# GTM900-breakout_v3.net
KiCad netlist of a schematic drawn in EAGLE
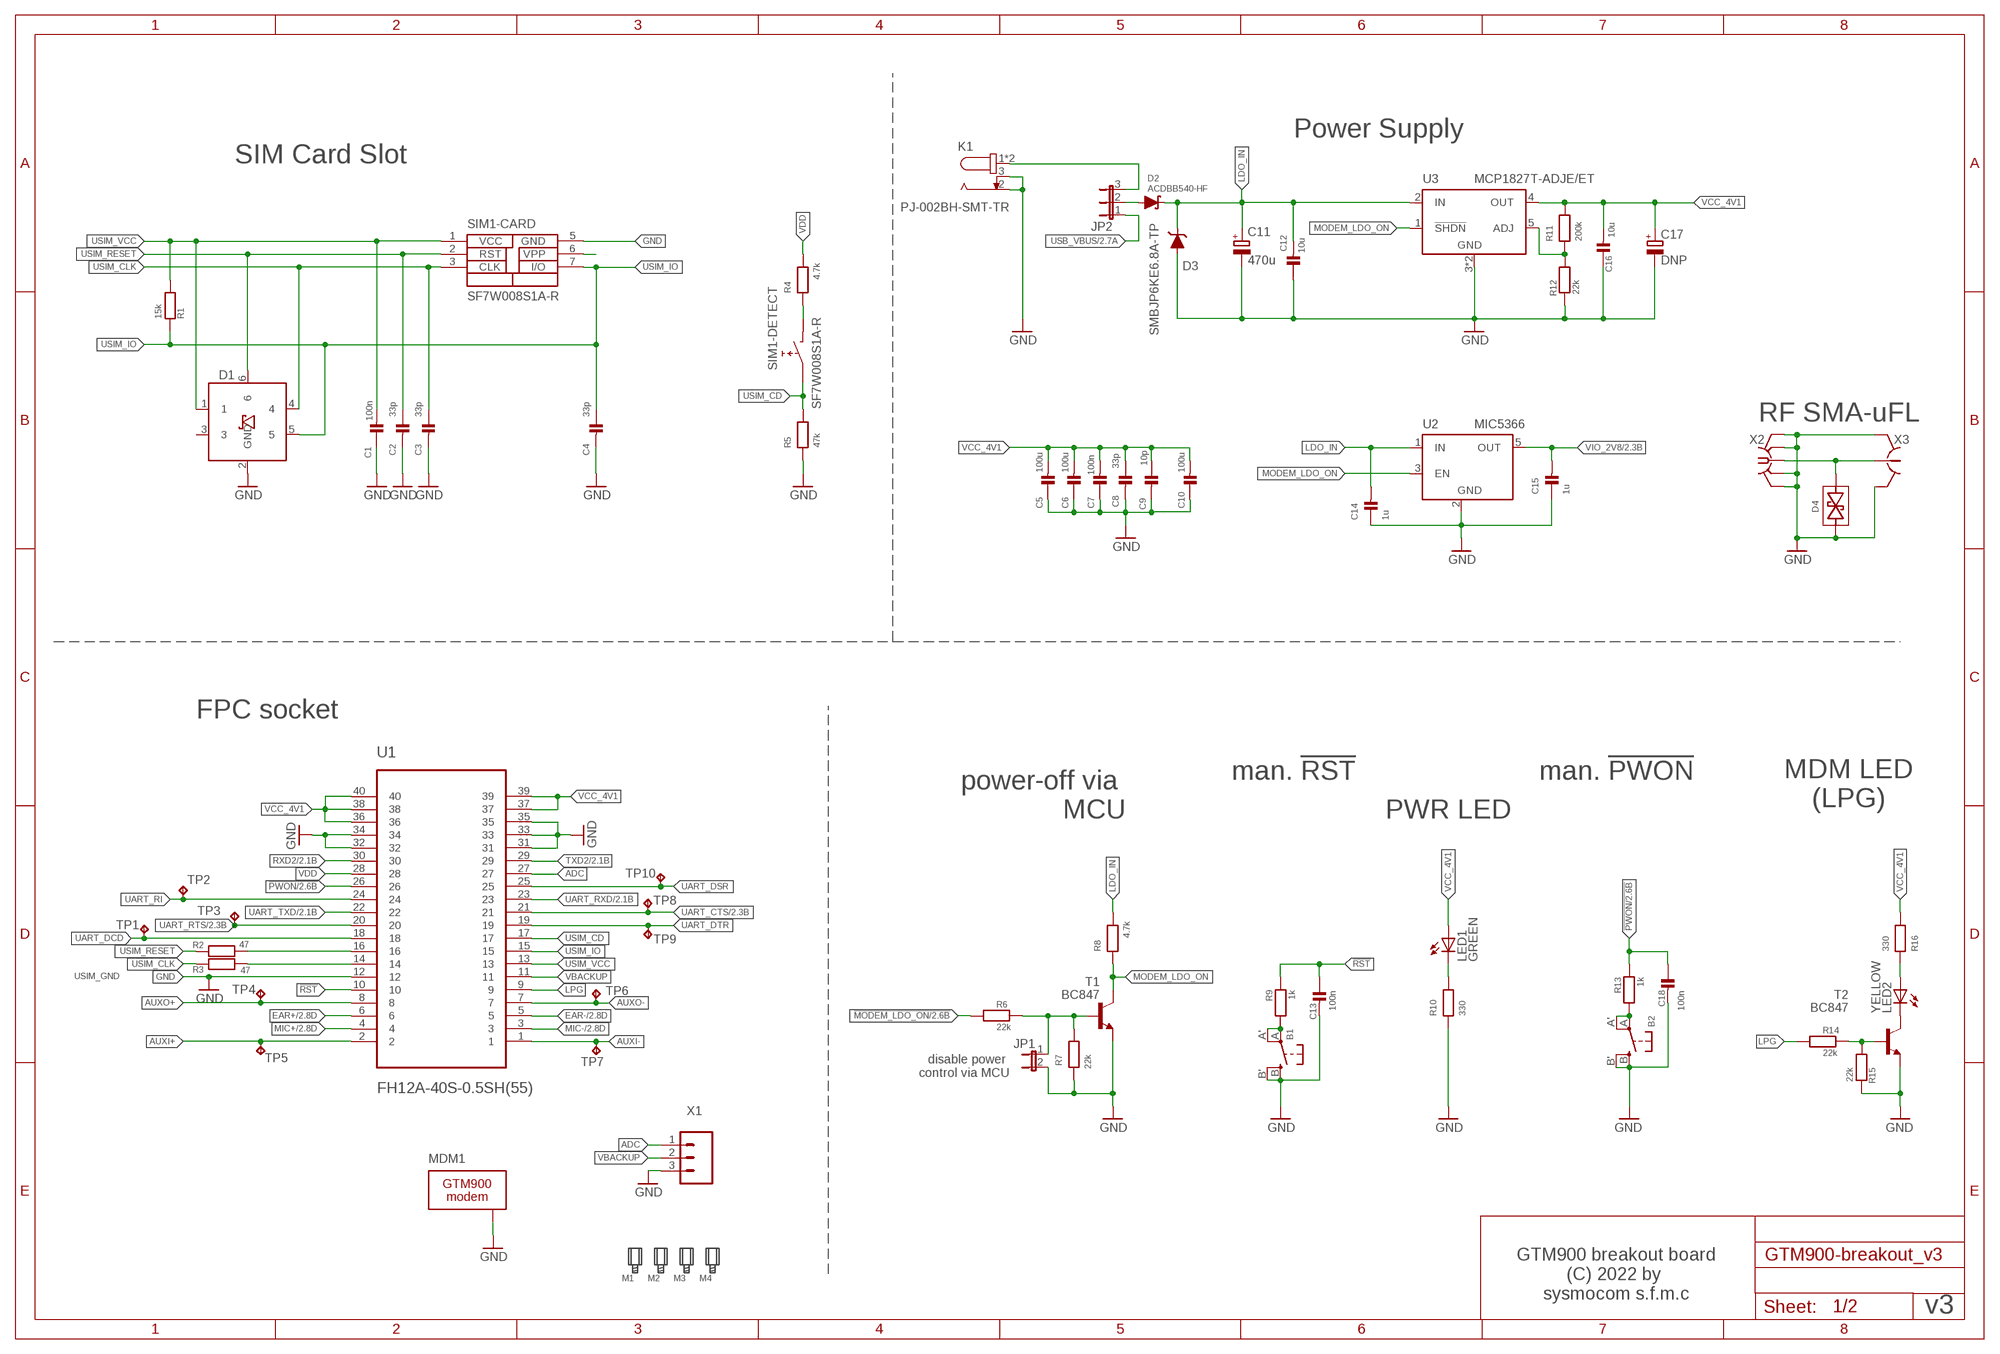
[diagram p0: schematic, sheet 1]
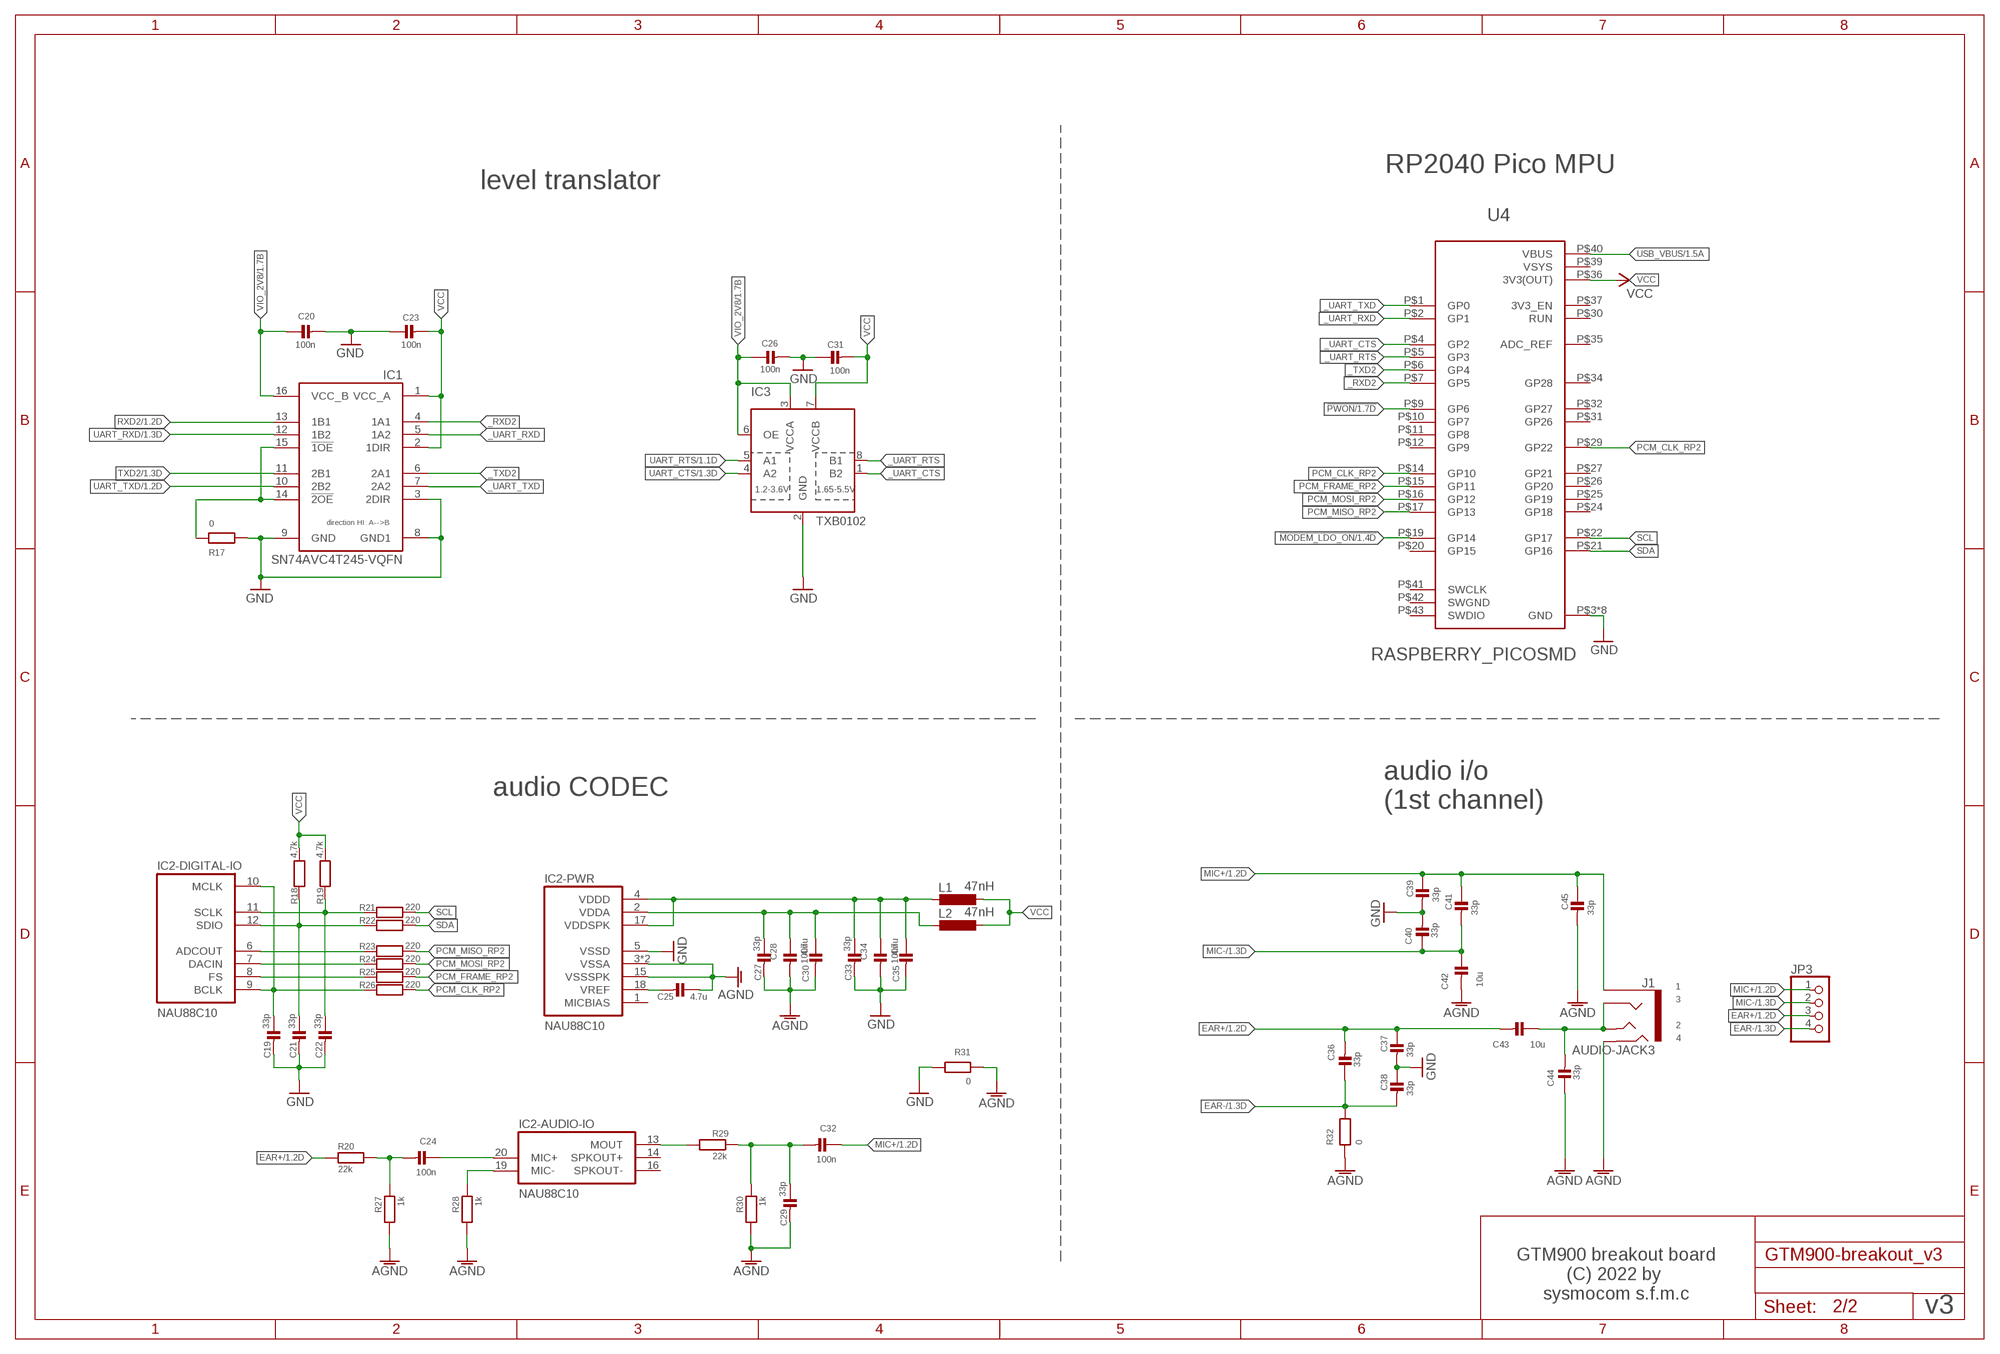
[diagram p1: schematic, sheet 2]

(export (version "E")
  (design (tool "Eeschema 10.0.6"))
  (components
    (comp (ref "C19")
      (value "33p")
      (footprint "eagle-import:_0402")
      (description "CAP CER 33PF 50V NP0 0402")
      (fields
        (field (name "MANUFACTURER") "Samsung Electro-Mechanics America, Inc.")
        (field (name "MANUFACTURERPARTNUMBER") "CL05C330JB5NNNC")
      )
      (libsource (lib "eagle-import") (part "CAP_CERAMIC_0402"))
    )
    (comp (ref "C20")
      (value "100n")
      (footprint "eagle-import:_0603")
      (description "CAP CER 0.1UF 16V X5R 0201")
      (fields
        (field (name "MANUFACTURER") "Murata Electronics")
        (field (name "MANUFACTURERPARTNUMBER") "GRM033R61C104KE84D")
      )
      (libsource (lib "eagle-import") (part "CAP_CERAMIC_0603"))
    )
    (comp (ref "C21")
      (value "33p")
      (footprint "eagle-import:_0402")
      (description "CAP CER 33PF 50V NP0 0402")
      (fields
        (field (name "MANUFACTURER") "Samsung Electro-Mechanics America, Inc.")
        (field (name "MANUFACTURERPARTNUMBER") "CL05C330JB5NNNC")
      )
      (libsource (lib "eagle-import") (part "CAP_CERAMIC_0402"))
    )
    (comp (ref "C22")
      (value "33p")
      (footprint "eagle-import:_0402")
      (description "CAP CER 33PF 50V NP0 0402")
      (fields
        (field (name "MANUFACTURER") "Samsung Electro-Mechanics America, Inc.")
        (field (name "MANUFACTURERPARTNUMBER") "CL05C330JB5NNNC")
      )
      (libsource (lib "eagle-import") (part "CAP_CERAMIC_0402"))
    )
    (comp (ref "C23")
      (value "100n")
      (footprint "eagle-import:_0603")
      (description "CAP CER 0.1UF 16V X5R 0201")
      (fields
        (field (name "MANUFACTURER") "Murata Electronics")
        (field (name "MANUFACTURERPARTNUMBER") "GRM033R61C104KE84D")
      )
      (libsource (lib "eagle-import") (part "CAP_CERAMIC_0603"))
    )
    (comp (ref "C24")
      (value "100n")
      (footprint "eagle-import:_0603")
      (description "CAP CER 0.1UF 16V X5R 0201")
      (fields
        (field (name "MANUFACTURER") "Murata Electronics")
        (field (name "MANUFACTURERPARTNUMBER") "GRM033R61C104KE84D")
      )
      (libsource (lib "eagle-import") (part "CAP_CERAMIC_0603"))
    )
    (comp (ref "C25")
      (value "4.7u")
      (footprint "eagle-import:_0603")
      (description "NO DESCRIPTION")
      (fields
        (field (name "MANUFACTURER") "UNKNOWN MANUFACTURER")
        (field (name "MANUFACTURERPARTNUMBER") "UNKNOWN MANUFACTURER PART NUMBER")
      )
      (libsource (lib "eagle-import") (part "CAP_CERAMIC_0603"))
    )
    (comp (ref "C26")
      (value "100n")
      (footprint "eagle-import:_0603")
      (description "CAP CER 0.1UF 16V X5R 0201")
      (fields
        (field (name "MANUFACTURER") "Murata Electronics")
        (field (name "MANUFACTURERPARTNUMBER") "GRM033R61C104KE84D")
      )
      (libsource (lib "eagle-import") (part "CAP_CERAMIC_0603"))
    )
    (comp (ref "C27")
      (value "33p")
      (footprint "eagle-import:_0402")
      (description "CAP CER 33PF 50V NP0 0402")
      (fields
        (field (name "MANUFACTURER") "Samsung Electro-Mechanics America, Inc.")
        (field (name "MANUFACTURERPARTNUMBER") "CL05C330JB5NNNC")
      )
      (libsource (lib "eagle-import") (part "CAP_CERAMIC_0402"))
    )
    (comp (ref "C28")
      (value "100n")
      (footprint "eagle-import:_0603")
      (description "CAP CER 0.1UF 16V X5R 0201")
      (fields
        (field (name "MANUFACTURER") "Murata Electronics")
        (field (name "MANUFACTURERPARTNUMBER") "GRM033R61C104KE84D")
      )
      (libsource (lib "eagle-import") (part "CAP_CERAMIC_0603"))
    )
    (comp (ref "C29")
      (value "33p")
      (footprint "eagle-import:_0402")
      (description "CAP CER 33PF 50V NP0 0402")
      (fields
        (field (name "MANUFACTURER") "Samsung Electro-Mechanics America, Inc.")
        (field (name "MANUFACTURERPARTNUMBER") "CL05C330JB5NNNC")
      )
      (libsource (lib "eagle-import") (part "CAP_CERAMIC_0402"))
    )
    (comp (ref "C30")
      (value "4.7u")
      (footprint "eagle-import:_0603")
      (description "NO DESCRIPTION")
      (fields
        (field (name "MANUFACTURER") "UNKNOWN MANUFACTURER")
        (field (name "MANUFACTURERPARTNUMBER") "UNKNOWN MANUFACTURER PART NUMBER")
      )
      (libsource (lib "eagle-import") (part "CAP_CERAMIC_0603"))
    )
    (comp (ref "C31")
      (value "100n")
      (footprint "eagle-import:_0603")
      (description "CAP CER 0.1UF 16V X5R 0201")
      (fields
        (field (name "MANUFACTURER") "Murata Electronics")
        (field (name "MANUFACTURERPARTNUMBER") "GRM033R61C104KE84D")
      )
      (libsource (lib "eagle-import") (part "CAP_CERAMIC_0603"))
    )
    (comp (ref "C32")
      (value "100n")
      (footprint "eagle-import:_0603")
      (description "CAP CER 0.1UF 16V X5R 0201")
      (fields
        (field (name "MANUFACTURER") "Murata Electronics")
        (field (name "MANUFACTURERPARTNUMBER") "GRM033R61C104KE84D")
      )
      (libsource (lib "eagle-import") (part "CAP_CERAMIC_0603"))
    )
    (comp (ref "C33")
      (value "33p")
      (footprint "eagle-import:_0402")
      (description "CAP CER 33PF 50V NP0 0402")
      (fields
        (field (name "MANUFACTURER") "Samsung Electro-Mechanics America, Inc.")
        (field (name "MANUFACTURERPARTNUMBER") "CL05C330JB5NNNC")
      )
      (libsource (lib "eagle-import") (part "CAP_CERAMIC_0402"))
    )
    (comp (ref "C34")
      (value "100n")
      (footprint "eagle-import:_0603")
      (description "CAP CER 0.1UF 16V X5R 0201")
      (fields
        (field (name "MANUFACTURER") "Murata Electronics")
        (field (name "MANUFACTURERPARTNUMBER") "GRM033R61C104KE84D")
      )
      (libsource (lib "eagle-import") (part "CAP_CERAMIC_0603"))
    )
    (comp (ref "C35")
      (value "4.7u")
      (footprint "eagle-import:_0603")
      (description "NO DESCRIPTION")
      (fields
        (field (name "MANUFACTURER") "UNKNOWN MANUFACTURER")
        (field (name "MANUFACTURERPARTNUMBER") "UNKNOWN MANUFACTURER PART NUMBER")
      )
      (libsource (lib "eagle-import") (part "CAP_CERAMIC_0603"))
    )
    (comp (ref "C36")
      (value "33p")
      (footprint "eagle-import:_0402")
      (description "CAP CER 33PF 50V NP0 0402")
      (fields
        (field (name "MANUFACTURER") "Samsung Electro-Mechanics America, Inc.")
        (field (name "MANUFACTURERPARTNUMBER") "CL05C330JB5NNNC")
      )
      (libsource (lib "eagle-import") (part "CAP_CERAMIC_0402"))
    )
    (comp (ref "C37")
      (value "33p")
      (footprint "eagle-import:_0402")
      (description "CAP CER 33PF 50V NP0 0402")
      (fields
        (field (name "MANUFACTURER") "Samsung Electro-Mechanics America, Inc.")
        (field (name "MANUFACTURERPARTNUMBER") "CL05C330JB5NNNC")
      )
      (libsource (lib "eagle-import") (part "CAP_CERAMIC_0402"))
    )
    (comp (ref "C38")
      (value "33p")
      (footprint "eagle-import:_0402")
      (description "CAP CER 33PF 50V NP0 0402")
      (fields
        (field (name "MANUFACTURER") "Samsung Electro-Mechanics America, Inc.")
        (field (name "MANUFACTURERPARTNUMBER") "CL05C330JB5NNNC")
      )
      (libsource (lib "eagle-import") (part "CAP_CERAMIC_0402"))
    )
    (comp (ref "C39")
      (value "33p")
      (footprint "eagle-import:_0402")
      (description "CAP CER 33PF 50V NP0 0402")
      (fields
        (field (name "MANUFACTURER") "Samsung Electro-Mechanics America, Inc.")
        (field (name "MANUFACTURERPARTNUMBER") "CL05C330JB5NNNC")
      )
      (libsource (lib "eagle-import") (part "CAP_CERAMIC_0402"))
    )
    (comp (ref "C40")
      (value "33p")
      (footprint "eagle-import:_0402")
      (description "CAP CER 33PF 50V NP0 0402")
      (fields
        (field (name "MANUFACTURER") "Samsung Electro-Mechanics America, Inc.")
        (field (name "MANUFACTURERPARTNUMBER") "CL05C330JB5NNNC")
      )
      (libsource (lib "eagle-import") (part "CAP_CERAMIC_0402"))
    )
    (comp (ref "C41")
      (value "33p")
      (footprint "eagle-import:_0402")
      (description "CAP CER 33PF 50V NP0 0402")
      (fields
        (field (name "MANUFACTURER") "Samsung Electro-Mechanics America, Inc.")
        (field (name "MANUFACTURERPARTNUMBER") "CL05C330JB5NNNC")
      )
      (libsource (lib "eagle-import") (part "CAP_CERAMIC_0402"))
    )
    (comp (ref "C42")
      (value "10u")
      (footprint "eagle-import:_0805")
      (description "CAP CER 10UF 16V X5R 0805")
      (fields
        (field (name "MANUFACTURER") "Murata Electronics")
        (field (name "MANUFACTURERPARTNUMBER") "GRM21BR61C106KE15K")
      )
      (libsource (lib "eagle-import") (part "CAP_CERAMIC_0805"))
    )
    (comp (ref "C43")
      (value "10u")
      (footprint "eagle-import:_0805")
      (description "CAP CER 10UF 16V X5R 0805")
      (fields
        (field (name "MANUFACTURER") "Murata Electronics")
        (field (name "MANUFACTURERPARTNUMBER") "GRM21BR61C106KE15K")
      )
      (libsource (lib "eagle-import") (part "CAP_CERAMIC_0805"))
    )
    (comp (ref "C44")
      (value "33p")
      (footprint "eagle-import:_0402")
      (description "CAP CER 33PF 50V NP0 0402")
      (fields
        (field (name "MANUFACTURER") "Samsung Electro-Mechanics America, Inc.")
        (field (name "MANUFACTURERPARTNUMBER") "CL05C330JB5NNNC")
      )
      (libsource (lib "eagle-import") (part "CAP_CERAMIC_0402"))
    )
    (comp (ref "C45")
      (value "33p")
      (footprint "eagle-import:_0402")
      (description "CAP CER 33PF 50V NP0 0402")
      (fields
        (field (name "MANUFACTURER") "Samsung Electro-Mechanics America, Inc.")
        (field (name "MANUFACTURERPARTNUMBER") "CL05C330JB5NNNC")
      )
      (libsource (lib "eagle-import") (part "CAP_CERAMIC_0402"))
    )
    (comp (ref "IC1")
      (value "SN74AVC4T245-VQFN")
      (footprint "eagle-import:VQFN-N16")
      (description "NO DESCRIPTION")
      (fields
        (field (name "MANUFACTURER") "UNKNOWN MANUFACTURER")
        (field (name "MANUFACTURERPARTNUMBER") "UNKNOWN MANUFACTURER PART NUMBER")
      )
      (libsource (lib "eagle-import") (part "SN74AVC4T245-VQFN"))
    )
    (comp (ref "IC2")
      (value "NAU88C10")
      (footprint "eagle-import:QFN20")
      (description "NO DESCRIPTION")
      (fields
        (field (name "CLASS") "UNKNOWN CLASS")
        (field (name "LINK") "UNKNOWN LINK")
        (field (name "MANUFACTURER") "UNKNOWN MANUFACTURER")
        (field (name "MANUFACTURERPARTNUMBER") "UNKNOWN MANUFACTURER PART NUMBER")
        (field (name "POPULATED") "TRUE")
        (field (name "ROHSCERTIFICATE") "UNKNOWN ROHS CERTIFICATE")
        (field (name "SOURCE") "UNKNOWN SOURCE")
        (field (name "SOURCEPARTNUMBER") "UNKNOWN SOURCE PART NUMBER")
      )
      (libsource (lib "eagle-import") (part "NAU88C10"))
    )
    (comp (ref "IC3")
      (value "TXB0102")
      (footprint "eagle-import:VSSOP-8")
      (description "NO DESCRIPTION")
      (fields
        (field (name "MANUFACTURER") "UNKNOWN MANUFACTURER")
        (field (name "MANUFACTURERPARTNUMBER") "UNKNOWN MANUFACTURER PART NUMBER")
      )
      (libsource (lib "eagle-import") (part "TXB0102"))
    )
    (comp (ref "J1")
      (value "AUDIO-JACK3")
      (footprint "eagle-import:AUDIO-JACK-TRRS-SMD")
      (description "AUDIO JACK, 3.5 MM, RT, 4 CONDUC")
      (fields
        (field (name "MANUFACTURER") "CUI Devices")
        (field (name "MANUFACTURERPARTNUMBER") "SJ2-3574A-SMT-TR")
      )
      (libsource (lib "eagle-import") (part "AUDIO-JACK3"))
    )
    (comp (ref "JP3")
      (value "HEADER-1X476MIL")
      (footprint "eagle-import:1X04_ROUND_76")
      (description "NO DESCRIPTION")
      (fields
        (field (name "MANUFACTURER") "UNKNOWN MANUFACTURER")
        (field (name "MANUFACTURERPARTNUMBER") "UNKNOWN MANUFACTURER PART NUMBER")
      )
      (libsource (lib "eagle-import") (part "HEADER-1X476MIL"))
    )
    (comp (ref "L1")
      (value "47nH")
      (footprint "eagle-import:_0603")
      (description "NO DESCRIPTION")
      (fields
        (field (name "MANUFACTURER") "UNKNOWN MANUFACTURER")
        (field (name "MANUFACTURERPARTNUMBER") "UNKNOWN MANUFACTURER PART NUMBER")
      )
      (libsource (lib "eagle-import") (part "INDUCTOR_0603"))
    )
    (comp (ref "L2")
      (value "47nH")
      (footprint "eagle-import:_0603")
      (description "NO DESCRIPTION")
      (fields
        (field (name "MANUFACTURER") "UNKNOWN MANUFACTURER")
        (field (name "MANUFACTURERPARTNUMBER") "UNKNOWN MANUFACTURER PART NUMBER")
      )
      (libsource (lib "eagle-import") (part "INDUCTOR_0603"))
    )
    (comp (ref "R17")
      (value "0")
      (footprint "eagle-import:_0603")
      (description "RES 0 OHM JUMPER 1/16W 0402")
      (fields
        (field (name "MANUFACTURER") "Stackpole Electronics Inc")
        (field (name "MANUFACTURERPARTNUMBER") "RMCF0402ZT0R00")
      )
      (libsource (lib "eagle-import") (part "RESISTOR_0603"))
    )
    (comp (ref "R18")
      (value "4,7k")
      (footprint "eagle-import:_0603")
      (description "NO DESCRIPTION")
      (fields
        (field (name "MANUFACTURER") "UNKNOWN MANUFACTURER")
        (field (name "MANUFACTURERPARTNUMBER") "UNKNOWN MANUFACTURER PART NUMBER")
      )
      (libsource (lib "eagle-import") (part "RESISTOR_0603"))
    )
    (comp (ref "R19")
      (value "4,7k")
      (footprint "eagle-import:_0603")
      (description "NO DESCRIPTION")
      (fields
        (field (name "MANUFACTURER") "UNKNOWN MANUFACTURER")
        (field (name "MANUFACTURERPARTNUMBER") "UNKNOWN MANUFACTURER PART NUMBER")
      )
      (libsource (lib "eagle-import") (part "RESISTOR_0603"))
    )
    (comp (ref "R20")
      (value "22k")
      (footprint "eagle-import:_0603")
      (description "RES SMD 22K OHM 1%% 1/10W 0603")
      (fields (field (name "MANUFACTURER") "Yageo") (field (name "MANUFACTURERPARTNUMBER") "RC0603FR-0722KL"))
      (libsource (lib "eagle-import") (part "RESISTOR_0603"))
    )
    (comp (ref "R21")
      (value "220")
      (footprint "eagle-import:_0603")
      (description "NO DESCRIPTION")
      (fields
        (field (name "MANUFACTURER") "UNKNOWN MANUFACTURER")
        (field (name "MANUFACTURERPARTNUMBER") "UNKNOWN MANUFACTURER PART NUMBER")
      )
      (libsource (lib "eagle-import") (part "RESISTOR_0603"))
    )
    (comp (ref "R22")
      (value "220")
      (footprint "eagle-import:_0603")
      (description "NO DESCRIPTION")
      (fields
        (field (name "MANUFACTURER") "UNKNOWN MANUFACTURER")
        (field (name "MANUFACTURERPARTNUMBER") "UNKNOWN MANUFACTURER PART NUMBER")
      )
      (libsource (lib "eagle-import") (part "RESISTOR_0603"))
    )
    (comp (ref "R23")
      (value "220")
      (footprint "eagle-import:_0603")
      (description "NO DESCRIPTION")
      (fields
        (field (name "MANUFACTURER") "UNKNOWN MANUFACTURER")
        (field (name "MANUFACTURERPARTNUMBER") "UNKNOWN MANUFACTURER PART NUMBER")
      )
      (libsource (lib "eagle-import") (part "RESISTOR_0603"))
    )
    (comp (ref "R24")
      (value "220")
      (footprint "eagle-import:_0603")
      (description "NO DESCRIPTION")
      (fields
        (field (name "MANUFACTURER") "UNKNOWN MANUFACTURER")
        (field (name "MANUFACTURERPARTNUMBER") "UNKNOWN MANUFACTURER PART NUMBER")
      )
      (libsource (lib "eagle-import") (part "RESISTOR_0603"))
    )
    (comp (ref "R25")
      (value "220")
      (footprint "eagle-import:_0603")
      (description "NO DESCRIPTION")
      (fields
        (field (name "MANUFACTURER") "UNKNOWN MANUFACTURER")
        (field (name "MANUFACTURERPARTNUMBER") "UNKNOWN MANUFACTURER PART NUMBER")
      )
      (libsource (lib "eagle-import") (part "RESISTOR_0603"))
    )
    (comp (ref "R26")
      (value "220")
      (footprint "eagle-import:_0603")
      (description "NO DESCRIPTION")
      (fields
        (field (name "MANUFACTURER") "UNKNOWN MANUFACTURER")
        (field (name "MANUFACTURERPARTNUMBER") "UNKNOWN MANUFACTURER PART NUMBER")
      )
      (libsource (lib "eagle-import") (part "RESISTOR_0603"))
    )
    (comp (ref "R27")
      (value "1k")
      (footprint "eagle-import:_0603")
      (description "NO DESCRIPTION")
      (fields
        (field (name "MANUFACTURER") "UNKNOWN MANUFACTURER")
        (field (name "MANUFACTURERPARTNUMBER") "UNKNOWN MANUFACTURER PART NUMBER")
      )
      (libsource (lib "eagle-import") (part "RESISTOR_0603"))
    )
    (comp (ref "R28")
      (value "1k")
      (footprint "eagle-import:_0603")
      (description "NO DESCRIPTION")
      (fields
        (field (name "MANUFACTURER") "UNKNOWN MANUFACTURER")
        (field (name "MANUFACTURERPARTNUMBER") "UNKNOWN MANUFACTURER PART NUMBER")
      )
      (libsource (lib "eagle-import") (part "RESISTOR_0603"))
    )
    (comp (ref "R29")
      (value "22k")
      (footprint "eagle-import:_0603")
      (description "RES SMD 22K OHM 1%% 1/10W 0603")
      (fields (field (name "MANUFACTURER") "Yageo") (field (name "MANUFACTURERPARTNUMBER") "RC0603FR-0722KL"))
      (libsource (lib "eagle-import") (part "RESISTOR_0603"))
    )
    (comp (ref "R30")
      (value "1k")
      (footprint "eagle-import:_0603")
      (description "NO DESCRIPTION")
      (fields
        (field (name "MANUFACTURER") "UNKNOWN MANUFACTURER")
        (field (name "MANUFACTURERPARTNUMBER") "UNKNOWN MANUFACTURER PART NUMBER")
      )
      (libsource (lib "eagle-import") (part "RESISTOR_0603"))
    )
    (comp (ref "R31")
      (value "0")
      (footprint "eagle-import:_0603")
      (description "RES 0 OHM JUMPER 1/16W 0402")
      (fields
        (field (name "MANUFACTURER") "Stackpole Electronics Inc")
        (field (name "MANUFACTURERPARTNUMBER") "RMCF0402ZT0R00")
      )
      (libsource (lib "eagle-import") (part "RESISTOR_0603"))
    )
    (comp (ref "R32")
      (value "0")
      (footprint "eagle-import:_0603")
      (description "RES 0 OHM JUMPER 1/16W 0402")
      (fields
        (field (name "MANUFACTURER") "Stackpole Electronics Inc")
        (field (name "MANUFACTURERPARTNUMBER") "RMCF0402ZT0R00")
      )
      (libsource (lib "eagle-import") (part "RESISTOR_0603"))
    )
    (comp (ref "U4")
      (value "RASPBERRY_PICOSMD")
      (footprint "eagle-import:PICO-PKG-SMD")
      (description "NO DESCRIPTION")
      (fields
        (field (name "MANUFACTURER") "UNKNOWN MANUFACTURER")
        (field (name "MANUFACTURERPARTNUMBER") "UNKNOWN MANUFACTURER PART NUMBER")
      )
      (libsource (lib "eagle-import") (part "RASPBERRY_PICOSMD"))
    )
    (comp (ref "B1")
      (value "SWITCH_TACT_SMT")
      (footprint "eagle-import:EVQ-Q2")
      (description "SWITCH TACTILE SPST-NO 0.02A 15V")
      (fields
        (field (name "MANUFACTURER") "Panasonic Electronic Components")
        (field (name "MANUFACTURERPARTNUMBER") "EVQ-Q2M03W")
      )
      (libsource (lib "eagle-import") (part "SWITCH_TACT_SMT"))
    )
    (comp (ref "B2")
      (value "SWITCH_TACT_SMT")
      (footprint "eagle-import:EVQ-Q2")
      (description "SWITCH TACTILE SPST-NO 0.02A 15V")
      (fields
        (field (name "MANUFACTURER") "Panasonic Electronic Components")
        (field (name "MANUFACTURERPARTNUMBER") "EVQ-Q2M03W")
      )
      (libsource (lib "eagle-import") (part "SWITCH_TACT_SMT"))
    )
    (comp (ref "C1")
      (value "100n")
      (footprint "eagle-import:_0603")
      (description "CAP CER 0.1UF 16V 10% X7R 0603")
      (fields
        (field (name "MANUFACTURER") "Samsung Electro-Mechanics America, Inc")
        (field (name "MANUFACTURERPARTNUMBER") "CL10B104KO8NNNC")
      )
      (libsource (lib "eagle-import") (part "CAP_CERAMIC_0603"))
    )
    (comp (ref "C2")
      (value "33p")
      (footprint "eagle-import:_0402")
      (description "CAP CER 33PF 50V NP0 0402")
      (fields
        (field (name "MANUFACTURER") "Samsung Electro-Mechanics America, Inc.")
        (field (name "MANUFACTURERPARTNUMBER") "CL05C330JB5NNNC")
      )
      (libsource (lib "eagle-import") (part "CAP_CERAMIC_0402"))
    )
    (comp (ref "C3")
      (value "33p")
      (footprint "eagle-import:_0402")
      (description "CAP CER 33PF 50V NP0 0402")
      (fields
        (field (name "MANUFACTURER") "Samsung Electro-Mechanics America, Inc.")
        (field (name "MANUFACTURERPARTNUMBER") "CL05C330JB5NNNC")
      )
      (libsource (lib "eagle-import") (part "CAP_CERAMIC_0402"))
    )
    (comp (ref "C4")
      (value "33p")
      (footprint "eagle-import:_0402")
      (description "CAP CER 33PF 50V NP0 0402")
      (fields
        (field (name "MANUFACTURER") "Samsung Electro-Mechanics America, Inc.")
        (field (name "MANUFACTURERPARTNUMBER") "CL05C330JB5NNNC")
      )
      (libsource (lib "eagle-import") (part "CAP_CERAMIC_0402"))
    )
    (comp (ref "C5")
      (value "100u")
      (footprint "eagle-import:1206")
      (description "CAP CER 100UF 6.3V X5R 1206")
      (fields
        (field (name "MANUFACTURER") "Murata Electronics")
        (field (name "MANUFACTURERPARTNUMBER") "GRM31CR60J107ME39K")
      )
      (libsource (lib "eagle-import") (part "CAP_CERAMIC1206"))
    )
    (comp (ref "C6")
      (value "100u")
      (footprint "eagle-import:1206")
      (description "CAP CER 100UF 6.3V X5R 1206")
      (fields
        (field (name "MANUFACTURER") "Murata Electronics")
        (field (name "MANUFACTURERPARTNUMBER") "GRM31CR60J107ME39K")
      )
      (libsource (lib "eagle-import") (part "CAP_CERAMIC1206"))
    )
    (comp (ref "C7")
      (value "100n")
      (footprint "eagle-import:_0603")
      (description "CAP CER 0.1UF 16V 10% X7R 0603")
      (fields
        (field (name "MANUFACTURER") "Samsung Electro-Mechanics America, Inc")
        (field (name "MANUFACTURERPARTNUMBER") "CL10B104KO8NNNC")
      )
      (libsource (lib "eagle-import") (part "CAP_CERAMIC_0603"))
    )
    (comp (ref "C8")
      (value "33p")
      (footprint "eagle-import:_0402")
      (description "CAP CER 33PF 50V NP0 0402")
      (fields
        (field (name "MANUFACTURER") "Samsung Electro-Mechanics America, Inc.")
        (field (name "MANUFACTURERPARTNUMBER") "CL05C330JB5NNNC")
      )
      (libsource (lib "eagle-import") (part "CAP_CERAMIC_0402"))
    )
    (comp (ref "C9")
      (value "10p")
      (footprint "eagle-import:_0603")
      (description "CAP CER 10PF 50V NP0 0603")
      (fields
        (field (name "MANUFACTURER") "Kemet")
        (field (name "MANUFACTURERPARTNUMBER") "C0603C100J5GACTU")
      )
      (libsource (lib "eagle-import") (part "CAP_CERAMIC_0603"))
    )
    (comp (ref "C10")
      (value "100u")
      (footprint "eagle-import:1206")
      (description "CAP CER 100UF 6.3V X5R 1206")
      (fields
        (field (name "MANUFACTURER") "Murata Electronics")
        (field (name "MANUFACTURERPARTNUMBER") "GRM31CR60J107ME39K")
      )
      (libsource (lib "eagle-import") (part "CAP_CERAMIC1206"))
    )
    (comp (ref "C11")
      (value "470u")
      (footprint "eagle-import:UD-8X10_NICHICON")
      (description "CAP ALUM 470UF 20%% 6.3V SMD")
      (fields
        (field (name "MANUFACTURER") "Nichicon")
        (field (name "MANUFACTURERPARTNUMBER") "UUR0J471MNL1GS")
      )
      (libsource (lib "eagle-import") (part "CPOL-EUUD-8X10"))
    )
    (comp (ref "C12")
      (value "10u")
      (footprint "eagle-import:_0805")
      (description "CAP CER 10UF 16V X5R 0805")
      (fields
        (field (name "MANUFACTURER") "Murata Electronics")
        (field (name "MANUFACTURERPARTNUMBER") "GRM21BR61C106KE15K")
      )
      (libsource (lib "eagle-import") (part "CAP_CERAMIC_0805"))
    )
    (comp (ref "C13")
      (value "100n")
      (footprint "eagle-import:_0603")
      (description "CAP CER 0.1UF 16V 10% X7R 0603")
      (fields
        (field (name "MANUFACTURER") "Samsung Electro-Mechanics America, Inc")
        (field (name "MANUFACTURERPARTNUMBER") "CL10B104KO8NNNC")
      )
      (libsource (lib "eagle-import") (part "CAP_CERAMIC_0603"))
    )
    (comp (ref "C14")
      (value "1u")
      (footprint "eagle-import:_0603")
      (description "CAP CER 1UF 16V X5R 0603")
      (fields
        (field (name "MANUFACTURER") "Samsung Electro-Mechanics")
        (field (name "MANUFACTURERPARTNUMBER") "CL10A105KO8NNNC")
      )
      (libsource (lib "eagle-import") (part "CAP_CERAMIC_0603"))
    )
    (comp (ref "C15")
      (value "1u")
      (footprint "eagle-import:_0603")
      (description "CAP CER 1UF 16V X5R 0603")
      (fields
        (field (name "MANUFACTURER") "Samsung Electro-Mechanics")
        (field (name "MANUFACTURERPARTNUMBER") "CL10A105KO8NNNC")
      )
      (libsource (lib "eagle-import") (part "CAP_CERAMIC_0603"))
    )
    (comp (ref "C16")
      (value "10u")
      (footprint "eagle-import:_0805")
      (description "CAP CER 10UF 16V X5R 0805")
      (fields
        (field (name "MANUFACTURER") "Murata Electronics")
        (field (name "MANUFACTURERPARTNUMBER") "GRM21BR61C106KE15K")
      )
      (libsource (lib "eagle-import") (part "CAP_CERAMIC_0805"))
    )
    (comp (ref "C17")
      (value "DNP")
      (footprint "eagle-import:SMC_E")
      (description "NO DESCRIPTION")
      (fields
        (field (name "MANUFACTURER") "UNKNOWN MANUFACTURER")
        (field (name "MANUFACTURERPARTNUMBER") "UNKNOWN MANUFACTURER PART NUMBER")
      )
      (libsource (lib "eagle-import") (part "CPOL-EUSMCE"))
    )
    (comp (ref "C18")
      (value "100n")
      (footprint "eagle-import:_0603")
      (description "CAP CER 0.1UF 16V 10% X7R 0603")
      (fields
        (field (name "MANUFACTURER") "Samsung Electro-Mechanics America, Inc")
        (field (name "MANUFACTURERPARTNUMBER") "CL10B104KO8NNNC")
      )
      (libsource (lib "eagle-import") (part "CAP_CERAMIC_0603"))
    )
    (comp (ref "D1")
      (value "PESD5V0UBV")
      (footprint "eagle-import:SOT666")
      (description "TVS DIODE 5V SOT666")
      (fields
        (field (name "MANUFACTURER") "Nexperia USA Inc.")
        (field (name "MANUFACTURERPARTNUMBER") "PESD5V0U5BV,115")
      )
      (libsource (lib "eagle-import") (part "PESD5V0UBV"))
    )
    (comp (ref "D2")
      (value "ACDBB540-HF")
      (footprint "eagle-import:SMBDIODE")
      (description "DIODE SCHOTTKY 40V 5A DO214AA")
      (fields (field (name "MANUFACTURER") "Comchip Technology"))
      (libsource (lib "eagle-import") (part "DIODE-SCHOTTKY-SMB"))
    )
    (comp (ref "D3")
      (value "SMBJP6KE6.8A-TP")
      (footprint "eagle-import:SMBDIODE")
      (description "TVS DIODE 5.8V 10.5V DO214AA")
      (fields (field (name "MANUFACTURER") "Micro Commercial Co"))
      (libsource (lib "eagle-import") (part "DIODE-TVS-SMB"))
    )
    (comp (ref "D4")
      (value "GG040205170N2P")
      (footprint "eagle-import:_0402")
      (description "TVS DIODE 5V 15.5V 0402")
      (fields
        (field (name "MANUFACTURER") "AVX Corporation")
        (field (name "MANUFACTURERPARTNUMBER") "GG0402050R3C2P")
      )
      (libsource (lib "eagle-import") (part "TVSDIODE-BIDI-0402"))
    )
    (comp (ref "JP1")
      (value "JP1E")
      (footprint "eagle-import:JP1")
      (description "NO DESCRIPTION")
      (fields
        (field (name "MANUFACTURER") "UNKNOWN MANUFACTURER")
        (field (name "MANUFACTURERPARTNUMBER") "UNKNOWN MANUFACTURER PART NUMBER")
      )
      (libsource (lib "eagle-import") (part "JP1E"))
    )
    (comp (ref "JP2")
      (value "JP2E")
      (footprint "eagle-import:JP2")
      (description "NO DESCRIPTION")
      (fields
        (field (name "MANUFACTURER") "UNKNOWN MANUFACTURER")
        (field (name "MANUFACTURERPARTNUMBER") "UNKNOWN MANUFACTURER PART NUMBER")
      )
      (libsource (lib "eagle-import") (part "JP2E"))
    )
    (comp (ref "K1")
      (value "PJ-002BH-SMT-TR")
      (footprint "eagle-import:694108106102")
      (description "CONN PWR JACK 2.5X5.5MM SOLDER")
      (fields (field (name "MANUFACTURER") "CUI Devices"))
      (libsource (lib "eagle-import") (part "694108106102"))
    )
    (comp (ref "LED1")
      (value "GREEN")
      (footprint "eagle-import:CHIP-LED0603")
      (description "NO DESCRIPTION")
      (fields
        (field (name "MANUFACTURER") "UNKNOWN MANUFACTURER")
        (field (name "MANUFACTURERPARTNUMBER") "UNKNOWN MANUFACTURER PART NUMBER")
      )
      (libsource (lib "eagle-import") (part "LEDCHIP-LED0603"))
    )
    (comp (ref "LED2")
      (value "YELLOW")
      (footprint "eagle-import:CHIP-LED0603")
      (description "NO DESCRIPTION")
      (fields
        (field (name "MANUFACTURER") "UNKNOWN MANUFACTURER")
        (field (name "MANUFACTURERPARTNUMBER") "UNKNOWN MANUFACTURER PART NUMBER")
      )
      (libsource (lib "eagle-import") (part "LEDCHIP-LED0603"))
    )
    (comp (ref "MDM1")
      (value "GTM900-BM2-SPACER")
      (footprint "eagle-import:GTM900-WRTHSPACER")
      (description "NO DESCRIPTION")
      (fields
        (field (name "MANUFACTURER") "UNKNOWN MANUFACTURER")
        (field (name "MANUFACTURERPARTNUMBER") "UNKNOWN MANUFACTURER PART NUMBER")
      )
      (libsource (lib "eagle-import") (part "GTM900-BM2-SPACER"))
    )
    (comp (ref "R1")
      (value "15k")
      (footprint "eagle-import:_0603")
      (description "RES SMD 15K OHM 1%% 1/10W 0603")
      (fields (field (name "MANUFACTURER") "Yageo") (field (name "MANUFACTURERPARTNUMBER") "RC0603FR-0715KL"))
      (libsource (lib "eagle-import") (part "RESISTOR_0603"))
    )
    (comp (ref "R2")
      (value "47")
      (footprint "eagle-import:_0603")
      (description "RES SMD 47 OHM 5%% 1/10W 0603")
      (fields (field (name "MANUFACTURER") "Yageo") (field (name "MANUFACTURERPARTNUMBER") "RC0603JR-0747RL"))
      (libsource (lib "eagle-import") (part "RESISTOR_0603"))
    )
    (comp (ref "R3")
      (value "47")
      (footprint "eagle-import:_0603")
      (description "RES SMD 47 OHM 5%% 1/10W 0603")
      (fields (field (name "MANUFACTURER") "Yageo") (field (name "MANUFACTURERPARTNUMBER") "RC0603JR-0747RL"))
      (libsource (lib "eagle-import") (part "RESISTOR_0603"))
    )
    (comp (ref "R4")
      (value "4.7k")
      (footprint "eagle-import:_0603")
      (description "RES SMD 4.7K OHM 5%% 1/10W 0603")
      (fields (field (name "MANUFACTURER") "Yageo") (field (name "MANUFACTURERPARTNUMBER") "RC0603JR-074K7L"))
      (libsource (lib "eagle-import") (part "RESISTOR_0603"))
    )
    (comp (ref "R5")
      (value "47k")
      (footprint "eagle-import:_0603")
      (description "RES SMD 47K OHM 1%% 1/10W 0603")
      (fields (field (name "MANUFACTURER") "Yageo") (field (name "MANUFACTURERPARTNUMBER") "RC0603FR-0747KL"))
      (libsource (lib "eagle-import") (part "RESISTOR_0603"))
    )
    (comp (ref "R6")
      (value "22k")
      (footprint "eagle-import:_0603")
      (description "RES SMD 22K OHM 1%% 1/10W 0603")
      (fields (field (name "MANUFACTURER") "Yageo") (field (name "MANUFACTURERPARTNUMBER") "RC0603FR-0722KL"))
      (libsource (lib "eagle-import") (part "RESISTOR_0603"))
    )
    (comp (ref "R7")
      (value "22k")
      (footprint "eagle-import:_0603")
      (description "RES SMD 22K OHM 1%% 1/10W 0603")
      (fields (field (name "MANUFACTURER") "Yageo") (field (name "MANUFACTURERPARTNUMBER") "RC0603FR-0722KL"))
      (libsource (lib "eagle-import") (part "RESISTOR_0603"))
    )
    (comp (ref "R8")
      (value "4.7k")
      (footprint "eagle-import:_0603")
      (description "RES SMD 4.7K OHM 5%% 1/10W 0603")
      (fields (field (name "MANUFACTURER") "Yageo") (field (name "MANUFACTURERPARTNUMBER") "RC0603JR-074K7L"))
      (libsource (lib "eagle-import") (part "RESISTOR_0603"))
    )
    (comp (ref "R9")
      (value "1k")
      (footprint "eagle-import:_0603")
      (description "RES SMD 1K OHM 0.5%% 1/16W 0603")
      (fields (field (name "MANUFACTURER") "Susumu") (field (name "MANUFACTURERPARTNUMBER") "RR0816P-102-D"))
      (libsource (lib "eagle-import") (part "RESISTOR_0603"))
    )
    (comp (ref "R10")
      (value "330")
      (footprint "eagle-import:_0603")
      (description "RES SMD 330 OHM 5%% 1/10W 0603")
      (fields
        (field (name "MANUFACTURER") "Yageo")
        (field (name "MANUFACTURERPARTNUMBER") "RC0603JR-07330RL")
      )
      (libsource (lib "eagle-import") (part "RESISTOR_0603"))
    )
    (comp (ref "R11")
      (value "200k")
      (footprint "eagle-import:_0603")
      (description "RES 200K OHM 1/16W 1% 0603")
      (fields
        (field (name "MANUFACTURER") "TE Connectivity")
        (field (name "MANUFACTURERPARTNUMBER") "8-1879338-5")
      )
      (libsource (lib "eagle-import") (part "RESISTOR_0603"))
    )
    (comp (ref "R12")
      (value "22k")
      (footprint "eagle-import:_0603")
      (description "RES SMD 22K OHM 1%% 1/10W 0603")
      (fields (field (name "MANUFACTURER") "Yageo") (field (name "MANUFACTURERPARTNUMBER") "RC0603FR-0722KL"))
      (libsource (lib "eagle-import") (part "RESISTOR_0603"))
    )
    (comp (ref "R13")
      (value "1k")
      (footprint "eagle-import:_0603")
      (description "RES SMD 1K OHM 0.5%% 1/16W 0603")
      (fields (field (name "MANUFACTURER") "Susumu") (field (name "MANUFACTURERPARTNUMBER") "RR0816P-102-D"))
      (libsource (lib "eagle-import") (part "RESISTOR_0603"))
    )
    (comp (ref "R14")
      (value "22k")
      (footprint "eagle-import:_0603")
      (description "RES SMD 22K OHM 1%% 1/10W 0603")
      (fields (field (name "MANUFACTURER") "Yageo") (field (name "MANUFACTURERPARTNUMBER") "RC0603FR-0722KL"))
      (libsource (lib "eagle-import") (part "RESISTOR_0603"))
    )
    (comp (ref "R15")
      (value "22k")
      (footprint "eagle-import:_0603")
      (description "RES SMD 22K OHM 1%% 1/10W 0603")
      (fields (field (name "MANUFACTURER") "Yageo") (field (name "MANUFACTURERPARTNUMBER") "RC0603FR-0722KL"))
      (libsource (lib "eagle-import") (part "RESISTOR_0603"))
    )
    (comp (ref "R16")
      (value "330")
      (footprint "eagle-import:_0603")
      (description "RES SMD 330 OHM 5%% 1/10W 0603")
      (fields
        (field (name "MANUFACTURER") "Yageo")
        (field (name "MANUFACTURERPARTNUMBER") "RC0603JR-07330RL")
      )
      (libsource (lib "eagle-import") (part "RESISTOR_0603"))
    )
    (comp (ref "SIM1")
      (value "SF7W008S1A-R")
      (footprint "eagle-import:SF7W008S1A-RESTR")
      (description "CONN SIM CARD HINGED TYPE R/A")
      (fields
        (field (name "MANUFACTURER") "JAE Electronics")
        (field (name "MANUFACTURERPARTNUMBER") "SF7W008S1AR900")
        (field (name "CLASS") "UNKNOWN CLASS")
        (field (name "LINK") "https://www.digikey.de/product-detail/de/jae-electronics/SF7W008S1AR900/670-2985-1-ND")
        (field (name "POPULATED") "TRUE")
        (field (name "ROHSCERTIFICATE") "UNKNOWN ROHS CERTIFICATE")
        (field (name "SOURCE") "DIGIKEY")
        (field (name "SOURCEPARTNUMBER") "670-2985-1-ND")
      )
      (libsource (lib "eagle-import") (part "SF7W008S1A-R"))
    )
    (comp (ref "T1")
      (value "BC847")
      (footprint "eagle-import:SOT23-BEC")
      (description "TRANS NPN 45V 0.1A SOT23")
      (fields
        (field (name "MANUFACTURER") "Nexperia USA Inc.")
        (field (name "MANUFACTURERPARTNUMBER") "BC847C,215")
      )
      (libsource (lib "eagle-import") (part "-NPN-SOT23-BECBC847C"))
    )
    (comp (ref "T2")
      (value "BC847")
      (footprint "eagle-import:SOT23-BEC")
      (description "TRANS NPN 45V 0.1A SOT23")
      (fields
        (field (name "MANUFACTURER") "Nexperia USA Inc.")
        (field (name "MANUFACTURERPARTNUMBER") "BC847C,215")
      )
      (libsource (lib "eagle-import") (part "-NPN-SOT23-BECBC847C"))
    )
    (comp (ref "TP1")
      (value "TPTP10R")
      (footprint "eagle-import:TP10R")
      (description "NO DESCRIPTION")
      (fields
        (field (name "MANUFACTURER") "UNKNOWN MANUFACTURER")
        (field (name "MANUFACTURERPARTNUMBER") "UNKNOWN MANUFACTURER PART NUMBER")
      )
      (libsource (lib "eagle-import") (part "TPTP10R"))
    )
    (comp (ref "TP2")
      (value "TPTP10R")
      (footprint "eagle-import:TP10R")
      (description "NO DESCRIPTION")
      (fields
        (field (name "MANUFACTURER") "UNKNOWN MANUFACTURER")
        (field (name "MANUFACTURERPARTNUMBER") "UNKNOWN MANUFACTURER PART NUMBER")
      )
      (libsource (lib "eagle-import") (part "TPTP10R"))
    )
    (comp (ref "TP3")
      (value "TPTP10R")
      (footprint "eagle-import:TP10R")
      (description "NO DESCRIPTION")
      (fields
        (field (name "MANUFACTURER") "UNKNOWN MANUFACTURER")
        (field (name "MANUFACTURERPARTNUMBER") "UNKNOWN MANUFACTURER PART NUMBER")
      )
      (libsource (lib "eagle-import") (part "TPTP10R"))
    )
    (comp (ref "TP4")
      (value "TPTP10R")
      (footprint "eagle-import:TP10R")
      (description "NO DESCRIPTION")
      (fields
        (field (name "MANUFACTURER") "UNKNOWN MANUFACTURER")
        (field (name "MANUFACTURERPARTNUMBER") "UNKNOWN MANUFACTURER PART NUMBER")
      )
      (libsource (lib "eagle-import") (part "TPTP10R"))
    )
    (comp (ref "TP5")
      (value "TPTP10R")
      (footprint "eagle-import:TP10R")
      (description "NO DESCRIPTION")
      (fields
        (field (name "MANUFACTURER") "UNKNOWN MANUFACTURER")
        (field (name "MANUFACTURERPARTNUMBER") "UNKNOWN MANUFACTURER PART NUMBER")
      )
      (libsource (lib "eagle-import") (part "TPTP10R"))
    )
    (comp (ref "TP6")
      (value "TPTP10R")
      (footprint "eagle-import:TP10R")
      (description "NO DESCRIPTION")
      (fields
        (field (name "MANUFACTURER") "UNKNOWN MANUFACTURER")
        (field (name "MANUFACTURERPARTNUMBER") "UNKNOWN MANUFACTURER PART NUMBER")
      )
      (libsource (lib "eagle-import") (part "TPTP10R"))
    )
    (comp (ref "TP7")
      (value "TPTP10R")
      (footprint "eagle-import:TP10R")
      (description "NO DESCRIPTION")
      (fields
        (field (name "MANUFACTURER") "UNKNOWN MANUFACTURER")
        (field (name "MANUFACTURERPARTNUMBER") "UNKNOWN MANUFACTURER PART NUMBER")
      )
      (libsource (lib "eagle-import") (part "TPTP10R"))
    )
    (comp (ref "TP8")
      (value "TPTP10R")
      (footprint "eagle-import:TP10R")
      (description "NO DESCRIPTION")
      (fields
        (field (name "MANUFACTURER") "UNKNOWN MANUFACTURER")
        (field (name "MANUFACTURERPARTNUMBER") "UNKNOWN MANUFACTURER PART NUMBER")
      )
      (libsource (lib "eagle-import") (part "TPTP10R"))
    )
    (comp (ref "TP9")
      (value "TPTP10R")
      (footprint "eagle-import:TP10R")
      (description "NO DESCRIPTION")
      (fields
        (field (name "MANUFACTURER") "UNKNOWN MANUFACTURER")
        (field (name "MANUFACTURERPARTNUMBER") "UNKNOWN MANUFACTURER PART NUMBER")
      )
      (libsource (lib "eagle-import") (part "TPTP10R"))
    )
    (comp (ref "TP10")
      (value "TPTP10R")
      (footprint "eagle-import:TP10R")
      (description "NO DESCRIPTION")
      (fields
        (field (name "MANUFACTURER") "UNKNOWN MANUFACTURER")
        (field (name "MANUFACTURERPARTNUMBER") "UNKNOWN MANUFACTURER PART NUMBER")
      )
      (libsource (lib "eagle-import") (part "TPTP10R"))
    )
    (comp (ref "U1")
      (value "FH12A-40S-0.5SH(55)")
      (footprint "eagle-import:HIROSE_FH12A-40S-0.5SH(55)")
      (description "CONN FFC TOP 40POS 0.50MM R/A")
      (fields (field (name "MANUFACTURER") "Hirose Electric Co Ltd"))
      (libsource (lib "eagle-import") (part "FH12A-40S-0.5SH(55)"))
    )
    (comp (ref "U2")
      (value "MIC5366")
      (footprint "eagle-import:SC70-5")
      (description "IC REG LINEAR 2.8V 150MA SC70-5")
      (fields
        (field (name "MANUFACTURER") "Microchip Technology")
        (field (name "MANUFACTURERPARTNUMBER") "MIC5366-2.8YC5-TR")
      )
      (libsource (lib "eagle-import") (part "LDO_FIXED_EN-MIC5365-YC5"))
    )
    (comp (ref "U3")
      (value "MCP1827T-ADJE/ET")
      (footprint "eagle-import:TI_KTT_DPAK2")
      (description "IC REG LIN POS ADJ 1.5A 5DDPAK")
      (fields (field (name "MANUFACTURER") "Microchip Technology"))
      (libsource (lib "eagle-import") (part "LDO_SHD_ADJMCP1827T-ADJE/ET"))
    )
    (comp (ref "X1")
      (value "PINHD-1X3PTH")
      (footprint "eagle-import:1X03")
      (description "NO DESCRIPTION")
      (fields
        (field (name "MANUFACTURER") "UNKNOWN MANUFACTURER")
        (field (name "MANUFACTURERPARTNUMBER") "UNKNOWN MANUFACTURER PART NUMBER")
      )
      (libsource (lib "eagle-import") (part "PINHD-1X3PTH"))
    )
    (comp (ref "X2")
      (value "SMA-F-S-TH")
      (footprint "eagle-import:SMA-F-S-TH")
      (description "CONN SMA JACK STR 50 OHM PCB")
      (fields
        (field (name "MANUFACTURER") "TE Connectivity AMP Connectors")
        (field (name "MANUFACTURERPARTNUMBER") "5-1814832-1")
      )
      (libsource (lib "eagle-import") (part "SMA-F-S-TH"))
    )
    (comp (ref "X3")
      (value "HRS_UFL")
      (footprint "eagle-import:HRS_UFL")
      (description "CONN U.FL RCPT STR 50 OHM SMD")
      (fields
        (field (name "MANUFACTURER") "Hirose Electric Co Ltd")
        (field (name "MANUFACTURERPARTNUMBER") "U.FL-R-SMT(01)")
      )
      (libsource (lib "eagle-import") (part "HRS_UFL"))
    )
  )
  (nets
    (net (code "1") (name "ADC") (class "Default")
      (node (ref "U1") (pin "27") (pinfunction "27_27") (pintype "passive"))
      (node (ref "X1") (pin "1") (pinfunction "1_1") (pintype "passive"))
    )
    (net (code "2") (name "AGND") (class "Default")
      (node (ref "C25") (pin "1") (pinfunction "1_1") (pintype "passive"))
      (node (ref "C27") (pin "2") (pinfunction "2_2") (pintype "passive"))
      (node (ref "C28") (pin "2") (pinfunction "2_2") (pintype "passive"))
      (node (ref "C29") (pin "2") (pinfunction "2_2") (pintype "passive"))
      (node (ref "C30") (pin "2") (pinfunction "2_2") (pintype "passive"))
      (node (ref "C42") (pin "2") (pinfunction "2_2") (pintype "passive"))
      (node (ref "C44") (pin "1") (pinfunction "1_1") (pintype "passive"))
      (node (ref "C45") (pin "2") (pinfunction "2_2") (pintype "passive"))
      (node (ref "IC2") (pin "15") (pinfunction "VSSSPK_15") (pintype "power_in"))
      (node (ref "IC2") (pin "3") (pinfunction "VSSA_3") (pintype "power_in"))
      (node (ref "IC2") (pin "EXP") (pinfunction "VSSA_EXP") (pintype "power_in"))
      (node (ref "J1") (pin "4") (pinfunction "RING2_4") (pintype "bidirectional"))
      (node (ref "R27") (pin "2") (pinfunction "2_2") (pintype "passive"))
      (node (ref "R28") (pin "2") (pinfunction "2_2") (pintype "passive"))
      (node (ref "R30") (pin "2") (pinfunction "2_2") (pintype "passive"))
      (node (ref "R31") (pin "1") (pinfunction "1_1") (pintype "passive"))
      (node (ref "R32") (pin "1") (pinfunction "1_1") (pintype "passive"))
    )
    (net (code "3") (name "AUXI+") (class "Default")
      (node (ref "TP5") (pin "TP") (pinfunction "TP_TP") (pintype "input"))
      (node (ref "U1") (pin "2") (pinfunction "2_2") (pintype "passive"))
    )
    (net (code "4") (name "AUXI-") (class "Default")
      (node (ref "TP7") (pin "TP") (pinfunction "TP_TP") (pintype "input"))
      (node (ref "U1") (pin "1") (pinfunction "1_1") (pintype "passive"))
    )
    (net (code "5") (name "AUXO+") (class "Default")
      (node (ref "TP4") (pin "TP") (pinfunction "TP_TP") (pintype "input"))
      (node (ref "U1") (pin "8") (pinfunction "8_8") (pintype "passive"))
    )
    (net (code "6") (name "AUXO-") (class "Default")
      (node (ref "TP6") (pin "TP") (pinfunction "TP_TP") (pintype "input"))
      (node (ref "U1") (pin "7") (pinfunction "7_7") (pintype "passive"))
    )
    (net (code "7") (name "EAR+") (class "Default")
      (node (ref "C36") (pin "2") (pinfunction "2_2") (pintype "passive"))
      (node (ref "C37") (pin "1") (pinfunction "1_1") (pintype "passive"))
      (node (ref "C43") (pin "2") (pinfunction "2_2") (pintype "passive"))
      (node (ref "JP3") (pin "3") (pinfunction "3_3") (pintype "passive"))
      (node (ref "R20") (pin "1") (pinfunction "1_1") (pintype "passive"))
      (node (ref "U1") (pin "6") (pinfunction "6_6") (pintype "passive"))
    )
    (net (code "8") (name "EAR-") (class "Default")
      (node (ref "C36") (pin "1") (pinfunction "1_1") (pintype "passive"))
      (node (ref "C38") (pin "2") (pinfunction "2_2") (pintype "passive"))
      (node (ref "JP3") (pin "4") (pinfunction "4_4") (pintype "passive"))
      (node (ref "R32") (pin "2") (pinfunction "2_2") (pintype "passive"))
      (node (ref "U1") (pin "5") (pinfunction "5_5") (pintype "passive"))
    )
    (net (code "9") (name "GND") (class "Default")
      (node (ref "B1") (pin "B") (pinfunction "S_B") (pintype "passive"))
      (node (ref "B1") (pin "B'") (pinfunction "S1_B'") (pintype "passive"))
      (node (ref "B2") (pin "B") (pinfunction "S_B") (pintype "passive"))
      (node (ref "B2") (pin "B'") (pinfunction "S1_B'") (pintype "passive"))
      (node (ref "C1") (pin "1") (pinfunction "1_1") (pintype "passive"))
      (node (ref "C10") (pin "1") (pinfunction "1_1") (pintype "passive"))
      (node (ref "C11") (pin "-") (pinfunction "-_-") (pintype "passive"))
      (node (ref "C12") (pin "1") (pinfunction "1_1") (pintype "passive"))
      (node (ref "C13") (pin "2") (pinfunction "2_2") (pintype "passive"))
      (node (ref "C14") (pin "1") (pinfunction "1_1") (pintype "passive"))
      (node (ref "C15") (pin "1") (pinfunction "1_1") (pintype "passive"))
      (node (ref "C16") (pin "1") (pinfunction "1_1") (pintype "passive"))
      (node (ref "C17") (pin "-") (pinfunction "-_-") (pintype "passive"))
      (node (ref "C18") (pin "2") (pinfunction "2_2") (pintype "passive"))
      (node (ref "C19") (pin "2") (pinfunction "2_2") (pintype "passive"))
      (node (ref "C2") (pin "2") (pinfunction "2_2") (pintype "passive"))
      (node (ref "C20") (pin "2") (pinfunction "2_2") (pintype "passive"))
      (node (ref "C21") (pin "2") (pinfunction "2_2") (pintype "passive"))
      (node (ref "C22") (pin "2") (pinfunction "2_2") (pintype "passive"))
      (node (ref "C23") (pin "1") (pinfunction "1_1") (pintype "passive"))
      (node (ref "C26") (pin "2") (pinfunction "2_2") (pintype "passive"))
      (node (ref "C3") (pin "2") (pinfunction "2_2") (pintype "passive"))
      (node (ref "C31") (pin "1") (pinfunction "1_1") (pintype "passive"))
      (node (ref "C33") (pin "2") (pinfunction "2_2") (pintype "passive"))
      (node (ref "C34") (pin "2") (pinfunction "2_2") (pintype "passive"))
      (node (ref "C35") (pin "2") (pinfunction "2_2") (pintype "passive"))
      (node (ref "C37") (pin "2") (pinfunction "2_2") (pintype "passive"))
      (node (ref "C38") (pin "1") (pinfunction "1_1") (pintype "passive"))
      (node (ref "C39") (pin "2") (pinfunction "2_2") (pintype "passive"))
      (node (ref "C4") (pin "2") (pinfunction "2_2") (pintype "passive"))
      (node (ref "C40") (pin "2") (pinfunction "2_2") (pintype "passive"))
      (node (ref "C5") (pin "1") (pinfunction "1_1") (pintype "passive"))
      (node (ref "C6") (pin "1") (pinfunction "1_1") (pintype "passive"))
      (node (ref "C7") (pin "1") (pinfunction "1_1") (pintype "passive"))
      (node (ref "C8") (pin "2") (pinfunction "2_2") (pintype "passive"))
      (node (ref "C9") (pin "2") (pinfunction "2_2") (pintype "passive"))
      (node (ref "D1") (pin "2") (pinfunction "GND_2") (pintype "passive"))
      (node (ref "D3") (pin "A") (pinfunction "A_A") (pintype "passive"))
      (node (ref "D4") (pin "1") (pinfunction "P$1_1") (pintype "bidirectional"))
      (node (ref "IC1") (pin "3") (pinfunction "2DIR_3") (pintype "input"))
      (node (ref "IC1") (pin "8") (pinfunction "GND1_8") (pintype "passive"))
      (node (ref "IC1") (pin "9") (pinfunction "GND_9") (pintype "passive"))
      (node (ref "IC2") (pin "5") (pinfunction "VSSD_5") (pintype "power_in"))
      (node (ref "IC3") (pin "2") (pinfunction "GND_2") (pintype "power_in"))
      (node (ref "JP1") (pin "2") (pinfunction "2_2") (pintype "passive"))
      (node (ref "K1") (pin "2") (pinfunction "2_2") (pintype "passive"))
      (node (ref "K1") (pin "3") (pinfunction "3_3") (pintype "passive"))
      (node (ref "MDM1") (pin "1") (pinfunction "P$1_1") (pintype "power_in"))
      (node (ref "MDM1") (pin "2") (pinfunction "P$1_2") (pintype "power_in"))
      (node (ref "MDM1") (pin "3") (pinfunction "P$1_3") (pintype "power_in"))
      (node (ref "MDM1") (pin "4") (pinfunction "P$1_4") (pintype "power_in"))
      (node (ref "R10") (pin "1") (pinfunction "1_1") (pintype "passive"))
      (node (ref "R12") (pin "2") (pinfunction "2_2") (pintype "passive"))
      (node (ref "R15") (pin "2") (pinfunction "2_2") (pintype "passive"))
      (node (ref "R17") (pin "2") (pinfunction "2_2") (pintype "passive"))
      (node (ref "R31") (pin "2") (pinfunction "2_2") (pintype "passive"))
      (node (ref "R5") (pin "1") (pinfunction "1_1") (pintype "passive"))
      (node (ref "R7") (pin "2") (pinfunction "2_2") (pintype "passive"))
      (node (ref "SIM1") (pin "5") (pinfunction "GND_5") (pintype "power_in"))
      (node (ref "T1") (pin "E") (pinfunction "E_E") (pintype "passive"))
      (node (ref "T2") (pin "E") (pinfunction "E_E") (pintype "passive"))
      (node (ref "U1") (pin "12") (pinfunction "12_12") (pintype "passive"))
      (node (ref "U1") (pin "31") (pinfunction "31_31") (pintype "passive"))
      (node (ref "U1") (pin "32") (pinfunction "32_32") (pintype "passive"))
      (node (ref "U1") (pin "33") (pinfunction "33_33") (pintype "passive"))
      (node (ref "U1") (pin "34") (pinfunction "34_34") (pintype "passive"))
      (node (ref "U1") (pin "35") (pinfunction "35_35") (pintype "passive"))
      (node (ref "U2") (pin "2") (pinfunction "GND_2") (pintype "power_in"))
      (node (ref "U3") (pin "3") (pinfunction "GND_3") (pintype "power_in"))
      (node (ref "U3") (pin "PAD") (pinfunction "GND_PAD") (pintype "power_in"))
      (node (ref "U4") (pin "P$13") (pinfunction "GND_P$13") (pintype "power_in"))
      (node (ref "U4") (pin "P$18") (pinfunction "GND_P$18") (pintype "power_in"))
      (node (ref "U4") (pin "P$23") (pinfunction "GND_P$23") (pintype "power_in"))
      (node (ref "U4") (pin "P$28") (pinfunction "GND_P$28") (pintype "power_in"))
      (node (ref "U4") (pin "P$3") (pinfunction "GND_P$3") (pintype "power_in"))
      (node (ref "U4") (pin "P$33") (pinfunction "GND_P$33") (pintype "power_in"))
      (node (ref "U4") (pin "P$38") (pinfunction "GND_P$38") (pintype "power_in"))
      (node (ref "U4") (pin "P$8") (pinfunction "GND_P$8") (pintype "power_in"))
      (node (ref "X1") (pin "3") (pinfunction "3_3") (pintype "passive"))
      (node (ref "X2") (pin "G1") (pinfunction "GND_G1") (pintype "power_in"))
      (node (ref "X2") (pin "G2") (pinfunction "GND_G2") (pintype "power_in"))
      (node (ref "X2") (pin "G3") (pinfunction "GND_G3") (pintype "power_in"))
      (node (ref "X2") (pin "G4") (pinfunction "GND_G4") (pintype "power_in"))
      (node (ref "X3") (pin "GND@1") (pinfunction "GND_GND@1") (pintype "power_in"))
      (node (ref "X3") (pin "GND@2") (pinfunction "GND_GND@2") (pintype "power_in"))
    )
    (net (code "10") (name "LDO_IN") (class "Default")
      (node (ref "C11") (pin "+") (pinfunction "+_+") (pintype "passive"))
      (node (ref "C12") (pin "2") (pinfunction "2_2") (pintype "passive"))
      (node (ref "C14") (pin "2") (pinfunction "2_2") (pintype "passive"))
      (node (ref "D2") (pin "C") (pinfunction "C_C") (pintype "passive"))
      (node (ref "D3") (pin "C") (pinfunction "C_C") (pintype "passive"))
      (node (ref "R8") (pin "2") (pinfunction "2_2") (pintype "passive"))
      (node (ref "U2") (pin "1") (pinfunction "IN_1") (pintype "input"))
      (node (ref "U3") (pin "2") (pinfunction "IN_2") (pintype "input"))
    )
    (net (code "11") (name "LPG") (class "Default")
      (node (ref "R14") (pin "1") (pinfunction "1_1") (pintype "passive"))
      (node (ref "U1") (pin "9") (pinfunction "9_9") (pintype "passive"))
    )
    (net (code "12") (name "MIC+") (class "Default")
      (node (ref "C32") (pin "1") (pinfunction "1_1") (pintype "passive"))
      (node (ref "C39") (pin "1") (pinfunction "1_1") (pintype "passive"))
      (node (ref "C41") (pin "1") (pinfunction "1_1") (pintype "passive"))
      (node (ref "C45") (pin "1") (pinfunction "1_1") (pintype "passive"))
      (node (ref "J1") (pin "1") (pinfunction "EARTH_1") (pintype "bidirectional"))
      (node (ref "JP3") (pin "1") (pinfunction "1_1") (pintype "passive"))
      (node (ref "U1") (pin "4") (pinfunction "4_4") (pintype "passive"))
    )
    (net (code "13") (name "MIC-") (class "Default")
      (node (ref "C40") (pin "1") (pinfunction "1_1") (pintype "passive"))
      (node (ref "C41") (pin "2") (pinfunction "2_2") (pintype "passive"))
      (node (ref "C42") (pin "1") (pinfunction "1_1") (pintype "passive"))
      (node (ref "JP3") (pin "2") (pinfunction "2_2") (pintype "passive"))
      (node (ref "U1") (pin "3") (pinfunction "3_3") (pintype "passive"))
    )
    (net (code "14") (name "MICBIAS") (class "Default")
      (node (ref "IC2") (pin "1") (pinfunction "MICBIAS_1") (pintype "power_in"))
    )
    (net (code "15") (name "MODEM_LDO_ON") (class "Default")
      (node (ref "R8") (pin "1") (pinfunction "1_1") (pintype "passive"))
      (node (ref "T1") (pin "C") (pinfunction "C_C") (pintype "passive"))
      (node (ref "U2") (pin "3") (pinfunction "EN_3") (pintype "input"))
      (node (ref "U3") (pin "1") (pinfunction "~{SHDN}_1") (pintype "input"))
    )
    (net (code "16") (name "Net-(B1-P)") (class "Default")
      (node (ref "B1") (pin "A") (pinfunction "P_A") (pintype "passive"))
      (node (ref "B1") (pin "A'") (pinfunction "P1_A'") (pintype "passive"))
      (node (ref "R9") (pin "2") (pinfunction "2_2") (pintype "passive"))
    )
    (net (code "17") (name "Net-(B2-P)") (class "Default")
      (node (ref "B2") (pin "A") (pinfunction "P_A") (pintype "passive"))
      (node (ref "B2") (pin "A'") (pinfunction "P1_A'") (pintype "passive"))
      (node (ref "R13") (pin "2") (pinfunction "2_2") (pintype "passive"))
    )
    (net (code "18") (name "Net-(C24-Pad2)") (class "Default")
      (node (ref "C24") (pin "2") (pinfunction "2_2") (pintype "passive"))
      (node (ref "R20") (pin "2") (pinfunction "2_2") (pintype "passive"))
      (node (ref "R27") (pin "1") (pinfunction "1_1") (pintype "passive"))
    )
    (net (code "19") (name "Net-(C29-Pad1)") (class "Default")
      (node (ref "C29") (pin "1") (pinfunction "1_1") (pintype "passive"))
      (node (ref "C32") (pin "2") (pinfunction "2_2") (pintype "passive"))
      (node (ref "R29") (pin "2") (pinfunction "2_2") (pintype "passive"))
      (node (ref "R30") (pin "1") (pinfunction "1_1") (pintype "passive"))
    )
    (net (code "20") (name "Net-(D2-PadA)") (class "Default")
      (node (ref "D2") (pin "A") (pinfunction "A_A") (pintype "passive"))
      (node (ref "JP2") (pin "2") (pinfunction "2_2") (pintype "passive"))
    )
    (net (code "21") (name "Net-(D4-P$2)") (class "Default")
      (node (ref "D4") (pin "2") (pinfunction "P$2_2") (pintype "bidirectional"))
      (node (ref "X2") (pin "C") (pinfunction "1_C") (pintype "passive"))
      (node (ref "X3") (pin "SIG") (pinfunction "1_SIG") (pintype "passive"))
    )
    (net (code "22") (name "Net-(IC1-~{1OE})") (class "Default")
      (node (ref "IC1") (pin "14") (pinfunction "~{2OE}_14") (pintype "input"))
      (node (ref "IC1") (pin "15") (pinfunction "~{1OE}_15") (pintype "input"))
      (node (ref "R17") (pin "1") (pinfunction "1_1") (pintype "passive"))
    )
    (net (code "23") (name "Net-(IC2A-MIC+)") (class "Default")
      (node (ref "C24") (pin "1") (pinfunction "1_1") (pintype "passive"))
      (node (ref "IC2") (pin "20") (pinfunction "MIC+_20") (pintype "power_in"))
    )
    (net (code "24") (name "Net-(IC2A-MIC-)") (class "Default")
      (node (ref "IC2") (pin "19") (pinfunction "MIC-_19") (pintype "power_in"))
      (node (ref "R28") (pin "1") (pinfunction "1_1") (pintype "passive"))
    )
    (net (code "25") (name "Net-(IC2A-MOUT)") (class "Default")
      (node (ref "IC2") (pin "13") (pinfunction "MOUT_13") (pintype "power_in"))
      (node (ref "R29") (pin "1") (pinfunction "1_1") (pintype "passive"))
    )
    (net (code "26") (name "Net-(IC2B-ADCOUT)") (class "Default")
      (node (ref "IC2") (pin "6") (pinfunction "ADCOUT_6") (pintype "power_in"))
      (node (ref "R23") (pin "1") (pinfunction "1_1") (pintype "passive"))
    )
    (net (code "27") (name "Net-(IC2B-BCLK)") (class "Default")
      (node (ref "C19") (pin "1") (pinfunction "1_1") (pintype "passive"))
      (node (ref "IC2") (pin "10") (pinfunction "MCLK_10") (pintype "power_in"))
      (node (ref "IC2") (pin "9") (pinfunction "BCLK_9") (pintype "power_in"))
      (node (ref "R26") (pin "1") (pinfunction "1_1") (pintype "passive"))
    )
    (net (code "28") (name "Net-(IC2B-DACIN)") (class "Default")
      (node (ref "IC2") (pin "7") (pinfunction "DACIN_7") (pintype "power_in"))
      (node (ref "R24") (pin "1") (pinfunction "1_1") (pintype "passive"))
    )
    (net (code "29") (name "Net-(IC2B-FS)") (class "Default")
      (node (ref "IC2") (pin "8") (pinfunction "FS_8") (pintype "power_in"))
      (node (ref "R25") (pin "1") (pinfunction "1_1") (pintype "passive"))
    )
    (net (code "30") (name "Net-(IC2B-SCLK)") (class "Default")
      (node (ref "C22") (pin "1") (pinfunction "1_1") (pintype "passive"))
      (node (ref "IC2") (pin "11") (pinfunction "SCLK_11") (pintype "power_in"))
      (node (ref "R19") (pin "1") (pinfunction "1_1") (pintype "passive"))
      (node (ref "R21") (pin "1") (pinfunction "1_1") (pintype "passive"))
    )
    (net (code "31") (name "Net-(IC2B-SDIO)") (class "Default")
      (node (ref "C21") (pin "1") (pinfunction "1_1") (pintype "passive"))
      (node (ref "IC2") (pin "12") (pinfunction "SDIO_12") (pintype "power_in"))
      (node (ref "R18") (pin "1") (pinfunction "1_1") (pintype "passive"))
      (node (ref "R22") (pin "1") (pinfunction "1_1") (pintype "passive"))
    )
    (net (code "32") (name "Net-(IC2C-VDDA)") (class "Default")
      (node (ref "C27") (pin "1") (pinfunction "1_1") (pintype "passive"))
      (node (ref "C28") (pin "1") (pinfunction "1_1") (pintype "passive"))
      (node (ref "C30") (pin "1") (pinfunction "1_1") (pintype "passive"))
      (node (ref "IC2") (pin "2") (pinfunction "VDDA_2") (pintype "power_in"))
      (node (ref "L2") (pin "2") (pinfunction "2_2") (pintype "passive"))
    )
    (net (code "33") (name "Net-(IC2C-VDDD)") (class "Default")
      (node (ref "C33") (pin "1") (pinfunction "1_1") (pintype "passive"))
      (node (ref "C34") (pin "1") (pinfunction "1_1") (pintype "passive"))
      (node (ref "C35") (pin "1") (pinfunction "1_1") (pintype "passive"))
      (node (ref "IC2") (pin "17") (pinfunction "VDDSPK_17") (pintype "power_in"))
      (node (ref "IC2") (pin "4") (pinfunction "VDDD_4") (pintype "power_in"))
      (node (ref "L1") (pin "2") (pinfunction "2_2") (pintype "passive"))
    )
    (net (code "34") (name "Net-(IC2C-VREF)") (class "Default")
      (node (ref "C25") (pin "2") (pinfunction "2_2") (pintype "passive"))
      (node (ref "IC2") (pin "18") (pinfunction "VREF_18") (pintype "power_in"))
    )
    (net (code "35") (name "Net-(J1-RING1)") (class "Default")
      (node (ref "C43") (pin "1") (pinfunction "1_1") (pintype "passive"))
      (node (ref "C44") (pin "2") (pinfunction "2_2") (pintype "passive"))
      (node (ref "J1") (pin "2") (pinfunction "TIP_2") (pintype "bidirectional"))
      (node (ref "J1") (pin "3") (pinfunction "RING1_3") (pintype "bidirectional"))
    )
    (net (code "36") (name "Net-(JP1-Pad1)") (class "Default")
      (node (ref "JP1") (pin "1") (pinfunction "1_1") (pintype "passive"))
      (node (ref "R6") (pin "2") (pinfunction "2_2") (pintype "passive"))
      (node (ref "R7") (pin "1") (pinfunction "1_1") (pintype "passive"))
      (node (ref "T1") (pin "B") (pinfunction "B_B") (pintype "passive"))
    )
    (net (code "37") (name "Net-(JP2-Pad3)") (class "Default")
      (node (ref "JP2") (pin "3") (pinfunction "3_3") (pintype "passive"))
      (node (ref "K1") (pin "1") (pinfunction "1_1") (pintype "passive"))
      (node (ref "K1") (pin "1-1") (pinfunction "1_1-1") (pintype "passive"))
    )
    (net (code "38") (name "Net-(LED1-PadC)") (class "Default")
      (node (ref "LED1") (pin "C") (pinfunction "C_C") (pintype "passive"))
      (node (ref "R10") (pin "2") (pinfunction "2_2") (pintype "passive"))
    )
    (net (code "39") (name "Net-(LED2-PadA)") (class "Default")
      (node (ref "LED2") (pin "A") (pinfunction "A_A") (pintype "passive"))
      (node (ref "R16") (pin "2") (pinfunction "2_2") (pintype "passive"))
    )
    (net (code "40") (name "Net-(LED2-PadC)") (class "Default")
      (node (ref "LED2") (pin "C") (pinfunction "C_C") (pintype "passive"))
      (node (ref "T2") (pin "C") (pinfunction "C_C") (pintype "passive"))
    )
    (net (code "41") (name "Net-(R2-Pad1)") (class "Default")
      (node (ref "R2") (pin "1") (pinfunction "1_1") (pintype "passive"))
      (node (ref "U1") (pin "16") (pinfunction "16_16") (pintype "passive"))
    )
    (net (code "42") (name "Net-(R3-Pad1)") (class "Default")
      (node (ref "R3") (pin "1") (pinfunction "1_1") (pintype "passive"))
      (node (ref "U1") (pin "14") (pinfunction "14_14") (pintype "passive"))
    )
    (net (code "43") (name "Net-(R14-Pad2)") (class "Default")
      (node (ref "R14") (pin "2") (pinfunction "2_2") (pintype "passive"))
      (node (ref "R15") (pin "1") (pinfunction "1_1") (pintype "passive"))
      (node (ref "T2") (pin "B") (pinfunction "B_B") (pintype "passive"))
    )
    (net (code "44") (name "Net-(SIM1B-1)") (class "Default")
      (node (ref "R4") (pin "1") (pinfunction "1_1") (pintype "passive"))
      (node (ref "SIM1") (pin "82") (pinfunction "1_82") (pintype "passive"))
    )
    (net (code "45") (name "Net-(U3-ADJ)") (class "Default")
      (node (ref "R11") (pin "1") (pinfunction "1_1") (pintype "passive"))
      (node (ref "R12") (pin "1") (pinfunction "1_1") (pintype "passive"))
      (node (ref "U3") (pin "5") (pinfunction "ADJ_5") (pintype "passive"))
    )
    (net (code "46") (name "PCM_CLK_RP2") (class "Default")
      (node (ref "R26") (pin "2") (pinfunction "2_2") (pintype "passive"))
      (node (ref "U4") (pin "P$14") (pinfunction "GP10_P$14") (pintype "bidirectional"))
      (node (ref "U4") (pin "P$29") (pinfunction "GP22_P$29") (pintype "bidirectional"))
    )
    (net (code "47") (name "PCM_FRAME_RP2") (class "Default")
      (node (ref "R25") (pin "2") (pinfunction "2_2") (pintype "passive"))
      (node (ref "U4") (pin "P$15") (pinfunction "GP11_P$15") (pintype "bidirectional"))
    )
    (net (code "48") (name "PCM_MISO_RP2") (class "Default")
      (node (ref "R23") (pin "2") (pinfunction "2_2") (pintype "passive"))
      (node (ref "U4") (pin "P$17") (pinfunction "GP13_P$17") (pintype "bidirectional"))
    )
    (net (code "49") (name "PCM_MOSI_RP2") (class "Default")
      (node (ref "R24") (pin "2") (pinfunction "2_2") (pintype "passive"))
      (node (ref "U4") (pin "P$16") (pinfunction "GP12_P$16") (pintype "bidirectional"))
    )
    (net (code "50") (name "RXD2") (class "Default")
      (node (ref "IC1") (pin "13") (pinfunction "1B1_13") (pintype "bidirectional"))
      (node (ref "U1") (pin "30") (pinfunction "30_30") (pintype "passive"))
    )
    (net (code "51") (name "SCL") (class "Default")
      (node (ref "R21") (pin "2") (pinfunction "2_2") (pintype "passive"))
      (node (ref "U4") (pin "P$22") (pinfunction "GP17_P$22") (pintype "bidirectional"))
    )
    (net (code "52") (name "SDA") (class "Default")
      (node (ref "R22") (pin "2") (pinfunction "2_2") (pintype "passive"))
      (node (ref "U4") (pin "P$21") (pinfunction "GP16_P$21") (pintype "bidirectional"))
    )
    (net (code "53") (name "SPKOUT+") (class "Default")
      (node (ref "IC2") (pin "14") (pinfunction "SPKOUT+_14") (pintype "power_in"))
    )
    (net (code "54") (name "SPKOUT-") (class "Default")
      (node (ref "IC2") (pin "16") (pinfunction "SPKOUT-_16") (pintype "power_in"))
    )
    (net (code "55") (name "SWGND") (class "Default")
      (node (ref "U4") (pin "P$42") (pinfunction "SWGND_P$42") (pintype "power_in"))
    )
    (net (code "56") (name "TXD2") (class "Default")
      (node (ref "IC1") (pin "11") (pinfunction "2B1_11") (pintype "bidirectional"))
      (node (ref "U1") (pin "29") (pinfunction "29_29") (pintype "passive"))
    )
    (net (code "57") (name "UART_CTS") (class "Default")
      (node (ref "IC3") (pin "4") (pinfunction "A2_4") (pintype "bidirectional"))
      (node (ref "TP8") (pin "TP") (pinfunction "TP_TP") (pintype "input"))
      (node (ref "U1") (pin "21") (pinfunction "21_21") (pintype "passive"))
    )
    (net (code "58") (name "UART_DCD") (class "Default")
      (node (ref "TP1") (pin "TP") (pinfunction "TP_TP") (pintype "input"))
      (node (ref "U1") (pin "18") (pinfunction "18_18") (pintype "passive"))
    )
    (net (code "59") (name "UART_DSR") (class "Default")
      (node (ref "TP10") (pin "TP") (pinfunction "TP_TP") (pintype "input"))
      (node (ref "U1") (pin "25") (pinfunction "25_25") (pintype "passive"))
    )
    (net (code "60") (name "UART_DTR") (class "Default")
      (node (ref "TP9") (pin "TP") (pinfunction "TP_TP") (pintype "input"))
      (node (ref "U1") (pin "19") (pinfunction "19_19") (pintype "passive"))
    )
    (net (code "61") (name "UART_RI") (class "Default")
      (node (ref "TP2") (pin "TP") (pinfunction "TP_TP") (pintype "input"))
      (node (ref "U1") (pin "24") (pinfunction "24_24") (pintype "passive"))
    )
    (net (code "62") (name "UART_RTS") (class "Default")
      (node (ref "IC3") (pin "5") (pinfunction "A1_5") (pintype "bidirectional"))
      (node (ref "TP3") (pin "TP") (pinfunction "TP_TP") (pintype "input"))
      (node (ref "U1") (pin "20") (pinfunction "20_20") (pintype "passive"))
    )
    (net (code "63") (name "UART_RXD") (class "Default")
      (node (ref "IC1") (pin "12") (pinfunction "1B2_12") (pintype "bidirectional"))
      (node (ref "U1") (pin "23") (pinfunction "23_23") (pintype "passive"))
    )
    (net (code "64") (name "UART_TXD") (class "Default")
      (node (ref "IC1") (pin "10") (pinfunction "2B2_10") (pintype "bidirectional"))
      (node (ref "U1") (pin "22") (pinfunction "22_22") (pintype "passive"))
    )
    (net (code "65") (name "USB_VBUS") (class "Default")
      (node (ref "JP2") (pin "1") (pinfunction "1_1") (pintype "passive"))
      (node (ref "U4") (pin "P$40") (pinfunction "VBUS_P$40") (pintype "power_in"))
    )
    (net (code "66") (name "USIM_CD") (class "Default")
      (node (ref "R5") (pin "2") (pinfunction "2_2") (pintype "passive"))
      (node (ref "SIM1") (pin "81") (pinfunction "0_81") (pintype "passive"))
      (node (ref "U1") (pin "17") (pinfunction "17_17") (pintype "passive"))
    )
    (net (code "67") (name "USIM_CLK") (class "Default")
      (node (ref "C3") (pin "1") (pinfunction "1_1") (pintype "passive"))
      (node (ref "D1") (pin "4") (pinfunction "4_4") (pintype "passive"))
      (node (ref "R3") (pin "2") (pinfunction "2_2") (pintype "passive"))
      (node (ref "SIM1") (pin "3") (pinfunction "CLK_3") (pintype "input"))
    )
    (net (code "68") (name "USIM_IO") (class "Default")
      (node (ref "C4") (pin "1") (pinfunction "1_1") (pintype "passive"))
      (node (ref "D1") (pin "5") (pinfunction "5_5") (pintype "passive"))
      (node (ref "R1") (pin "1") (pinfunction "1_1") (pintype "passive"))
      (node (ref "SIM1") (pin "7") (pinfunction "I/O_7") (pintype "bidirectional"))
      (node (ref "U1") (pin "15") (pinfunction "15_15") (pintype "passive"))
    )
    (net (code "69") (name "USIM_RESET") (class "Default")
      (node (ref "C2") (pin "1") (pinfunction "1_1") (pintype "passive"))
      (node (ref "D1") (pin "6") (pinfunction "6_6") (pintype "passive"))
      (node (ref "R2") (pin "2") (pinfunction "2_2") (pintype "passive"))
      (node (ref "SIM1") (pin "2") (pinfunction "RST_2") (pintype "input"))
    )
    (net (code "70") (name "USIM_VCC") (class "Default")
      (node (ref "C1") (pin "2") (pinfunction "2_2") (pintype "passive"))
      (node (ref "D1") (pin "1") (pinfunction "1_1") (pintype "passive"))
      (node (ref "R1") (pin "2") (pinfunction "2_2") (pintype "passive"))
      (node (ref "SIM1") (pin "1") (pinfunction "VCC_1") (pintype "power_in"))
      (node (ref "U1") (pin "13") (pinfunction "13_13") (pintype "passive"))
    )
    (net (code "71") (name "VBACKUP") (class "Default")
      (node (ref "U1") (pin "11") (pinfunction "11_11") (pintype "passive"))
      (node (ref "X1") (pin "2") (pinfunction "2_2") (pintype "passive"))
    )
    (net (code "72") (name "VCC") (class "Default")
      (node (ref "C23") (pin "2") (pinfunction "2_2") (pintype "passive"))
      (node (ref "C31") (pin "2") (pinfunction "2_2") (pintype "passive"))
      (node (ref "IC1") (pin "1") (pinfunction "VCC_A_1") (pintype "bidirectional"))
      (node (ref "IC1") (pin "2") (pinfunction "1DIR_2") (pintype "input"))
      (node (ref "IC3") (pin "7") (pinfunction "VCCB_7") (pintype "power_in"))
      (node (ref "L1") (pin "1") (pinfunction "1_1") (pintype "passive"))
      (node (ref "L2") (pin "1") (pinfunction "1_1") (pintype "passive"))
      (node (ref "R18") (pin "2") (pinfunction "2_2") (pintype "passive"))
      (node (ref "R19") (pin "2") (pinfunction "2_2") (pintype "passive"))
      (node (ref "U4") (pin "P$36") (pinfunction "3V3(OUT)_P$36") (pintype "power_in"))
    )
    (net (code "73") (name "VCC_4V1") (class "Default")
      (node (ref "C10") (pin "2") (pinfunction "2_2") (pintype "passive"))
      (node (ref "C16") (pin "2") (pinfunction "2_2") (pintype "passive"))
      (node (ref "C17") (pin "+") (pinfunction "+_+") (pintype "passive"))
      (node (ref "C5") (pin "2") (pinfunction "2_2") (pintype "passive"))
      (node (ref "C6") (pin "2") (pinfunction "2_2") (pintype "passive"))
      (node (ref "C7") (pin "2") (pinfunction "2_2") (pintype "passive"))
      (node (ref "C8") (pin "1") (pinfunction "1_1") (pintype "passive"))
      (node (ref "C9") (pin "1") (pinfunction "1_1") (pintype "passive"))
      (node (ref "LED1") (pin "A") (pinfunction "A_A") (pintype "passive"))
      (node (ref "R11") (pin "2") (pinfunction "2_2") (pintype "passive"))
      (node (ref "R16") (pin "1") (pinfunction "1_1") (pintype "passive"))
      (node (ref "U1") (pin "36") (pinfunction "36_36") (pintype "passive"))
      (node (ref "U1") (pin "37") (pinfunction "37_37") (pintype "passive"))
      (node (ref "U1") (pin "38") (pinfunction "38_38") (pintype "passive"))
      (node (ref "U1") (pin "39") (pinfunction "39_39") (pintype "passive"))
      (node (ref "U1") (pin "40") (pinfunction "40_40") (pintype "passive"))
      (node (ref "U3") (pin "4") (pinfunction "OUT_4") (pintype "passive"))
    )
    (net (code "74") (name "VDD") (class "Default")
      (node (ref "R4") (pin "2") (pinfunction "2_2") (pintype "passive"))
      (node (ref "U1") (pin "28") (pinfunction "28_28") (pintype "passive"))
    )
    (net (code "75") (name "VIO_2V8") (class "Default")
      (node (ref "C15") (pin "2") (pinfunction "2_2") (pintype "passive"))
      (node (ref "C20") (pin "1") (pinfunction "1_1") (pintype "passive"))
      (node (ref "C26") (pin "1") (pinfunction "1_1") (pintype "passive"))
      (node (ref "IC1") (pin "16") (pinfunction "VCC_B_16") (pintype "power_in"))
      (node (ref "IC3") (pin "3") (pinfunction "VCCA_3") (pintype "power_in"))
      (node (ref "IC3") (pin "6") (pinfunction "OE_6") (pintype "input"))
      (node (ref "U2") (pin "5") (pinfunction "OUT_5") (pintype "passive"))
    )
    (net (code "76") (name "VSYS") (class "Default")
      (node (ref "U4") (pin "P$39") (pinfunction "VSYS_P$39") (pintype "power_in"))
    )
    (net (code "77") (name "_RXD2") (class "Default")
      (node (ref "IC1") (pin "4") (pinfunction "1A1_4") (pintype "bidirectional"))
      (node (ref "U4") (pin "P$7") (pinfunction "GP5_P$7") (pintype "bidirectional"))
    )
    (net (code "78") (name "_TXD2") (class "Default")
      (node (ref "IC1") (pin "6") (pinfunction "2A1_6") (pintype "bidirectional"))
      (node (ref "U4") (pin "P$6") (pinfunction "GP4_P$6") (pintype "bidirectional"))
    )
    (net (code "79") (name "_UART_CTS") (class "Default")
      (node (ref "IC3") (pin "1") (pinfunction "B2_1") (pintype "bidirectional"))
      (node (ref "U4") (pin "P$4") (pinfunction "GP2_P$4") (pintype "bidirectional"))
    )
    (net (code "80") (name "_UART_RTS") (class "Default")
      (node (ref "IC3") (pin "8") (pinfunction "B1_8") (pintype "bidirectional"))
      (node (ref "U4") (pin "P$5") (pinfunction "GP3_P$5") (pintype "bidirectional"))
    )
    (net (code "81") (name "_UART_RXD") (class "Default")
      (node (ref "IC1") (pin "5") (pinfunction "1A2_5") (pintype "bidirectional"))
      (node (ref "U4") (pin "P$2") (pinfunction "GP1_P$2") (pintype "bidirectional"))
    )
    (net (code "82") (name "_UART_TXD") (class "Default")
      (node (ref "IC1") (pin "7") (pinfunction "2A2_7") (pintype "bidirectional"))
      (node (ref "U4") (pin "P$1") (pinfunction "GP0_P$1") (pintype "bidirectional"))
    )
    (net (code "83") (name "unconnected-(D1-Pad3)") (class "Default")
      (node (ref "D1") (pin "3") (pinfunction "3_3") (pintype "passive"))
    )
    (net (code "84") (name "unconnected-(SIM1A-VPP-Pad6)") (class "Default")
      (node (ref "SIM1") (pin "6") (pinfunction "VPP_6") (pintype "power_in"))
    )
    (net (code "85") (name "unconnected-(U4-3V3_EN-PadP$37)") (class "Default")
      (node (ref "U4") (pin "P$37") (pinfunction "3V3_EN_P$37") (pintype "input"))
    )
    (net (code "86") (name "unconnected-(U4-ADC_REF-PadP$35)") (class "Default")
      (node (ref "U4") (pin "P$35") (pinfunction "ADC_REF_P$35") (pintype "input"))
    )
    (net (code "87") (name "unconnected-(U4-GP7-PadP$10)") (class "Default")
      (node (ref "U4") (pin "P$10") (pinfunction "GP7_P$10") (pintype "bidirectional"))
    )
    (net (code "88") (name "unconnected-(U4-GP8-PadP$11)") (class "Default")
      (node (ref "U4") (pin "P$11") (pinfunction "GP8_P$11") (pintype "bidirectional"))
    )
    (net (code "89") (name "unconnected-(U4-GP9-PadP$12)") (class "Default")
      (node (ref "U4") (pin "P$12") (pinfunction "GP9_P$12") (pintype "bidirectional"))
    )
    (net (code "90") (name "unconnected-(U4-GP15-PadP$20)") (class "Default")
      (node (ref "U4") (pin "P$20") (pinfunction "GP15_P$20") (pintype "bidirectional"))
    )
    (net (code "91") (name "unconnected-(U4-GP18-PadP$24)") (class "Default")
      (node (ref "U4") (pin "P$24") (pinfunction "GP18_P$24") (pintype "bidirectional"))
    )
    (net (code "92") (name "unconnected-(U4-GP19-PadP$25)") (class "Default")
      (node (ref "U4") (pin "P$25") (pinfunction "GP19_P$25") (pintype "bidirectional"))
    )
    (net (code "93") (name "unconnected-(U4-GP20-PadP$26)") (class "Default")
      (node (ref "U4") (pin "P$26") (pinfunction "GP20_P$26") (pintype "bidirectional"))
    )
    (net (code "94") (name "unconnected-(U4-GP21-PadP$27)") (class "Default")
      (node (ref "U4") (pin "P$27") (pinfunction "GP21_P$27") (pintype "bidirectional"))
    )
    (net (code "95") (name "unconnected-(U4-GP26-PadP$31)") (class "Default")
      (node (ref "U4") (pin "P$31") (pinfunction "GP26_P$31") (pintype "bidirectional"))
    )
    (net (code "96") (name "unconnected-(U4-GP27-PadP$32)") (class "Default")
      (node (ref "U4") (pin "P$32") (pinfunction "GP27_P$32") (pintype "bidirectional"))
    )
    (net (code "97") (name "unconnected-(U4-GP28-PadP$34)") (class "Default")
      (node (ref "U4") (pin "P$34") (pinfunction "GP28_P$34") (pintype "bidirectional"))
    )
    (net (code "98") (name "unconnected-(U4-RUN-PadP$30)") (class "Default")
      (node (ref "U4") (pin "P$30") (pinfunction "RUN_P$30") (pintype "input"))
    )
    (net (code "99") (name "unconnected-(U4-SWCLK-PadP$41)") (class "Default")
      (node (ref "U4") (pin "P$41") (pinfunction "SWCLK_P$41") (pintype "input"))
    )
    (net (code "100") (name "unconnected-(U4-SWDIO-PadP$43)") (class "Default")
      (node (ref "U4") (pin "P$43") (pinfunction "SWDIO_P$43") (pintype "bidirectional"))
    )
    (net (code "101") (name "~{MODEM_LDO_ON}") (class "Default")
      (node (ref "R6") (pin "1") (pinfunction "1_1") (pintype "passive"))
      (node (ref "U4") (pin "P$19") (pinfunction "GP14_P$19") (pintype "bidirectional"))
    )
    (net (code "102") (name "~{PWON}") (class "Default")
      (node (ref "C18") (pin "1") (pinfunction "1_1") (pintype "passive"))
      (node (ref "R13") (pin "1") (pinfunction "1_1") (pintype "passive"))
      (node (ref "U1") (pin "26") (pinfunction "26_26") (pintype "passive"))
      (node (ref "U4") (pin "P$9") (pinfunction "GP6_P$9") (pintype "bidirectional"))
    )
    (net (code "103") (name "~{RST}") (class "Default")
      (node (ref "C13") (pin "1") (pinfunction "1_1") (pintype "passive"))
      (node (ref "R9") (pin "1") (pinfunction "1_1") (pintype "passive"))
      (node (ref "U1") (pin "10") (pinfunction "10_10") (pintype "passive"))
    )
  )
)
